# main.net
KiCad netlist of a schematic drawn in Altium Designer
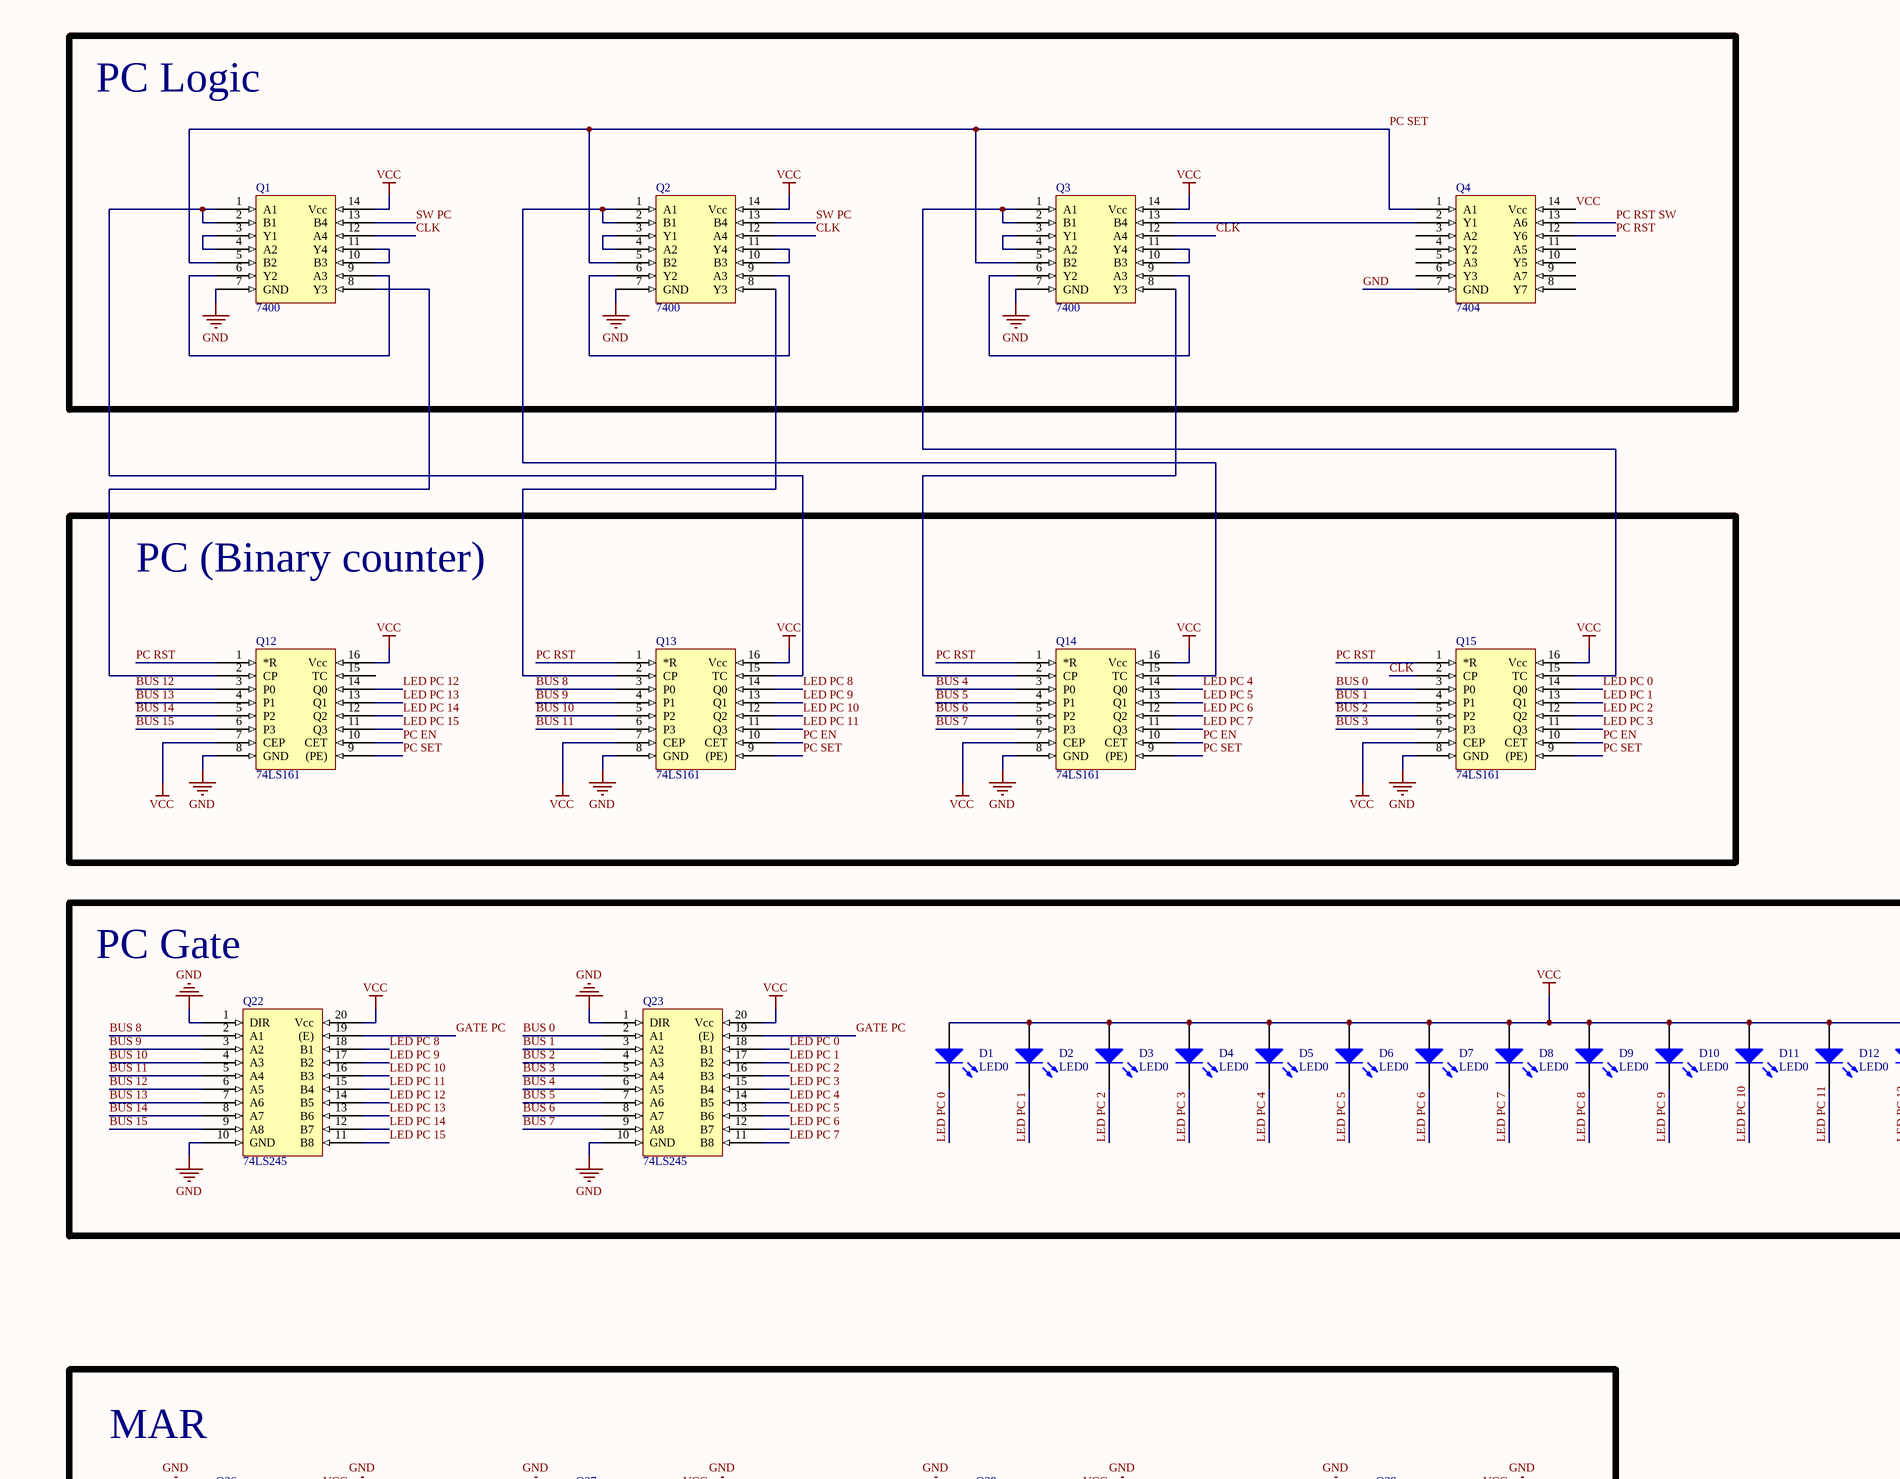
[diagram p0: main.SchDoc, top left]
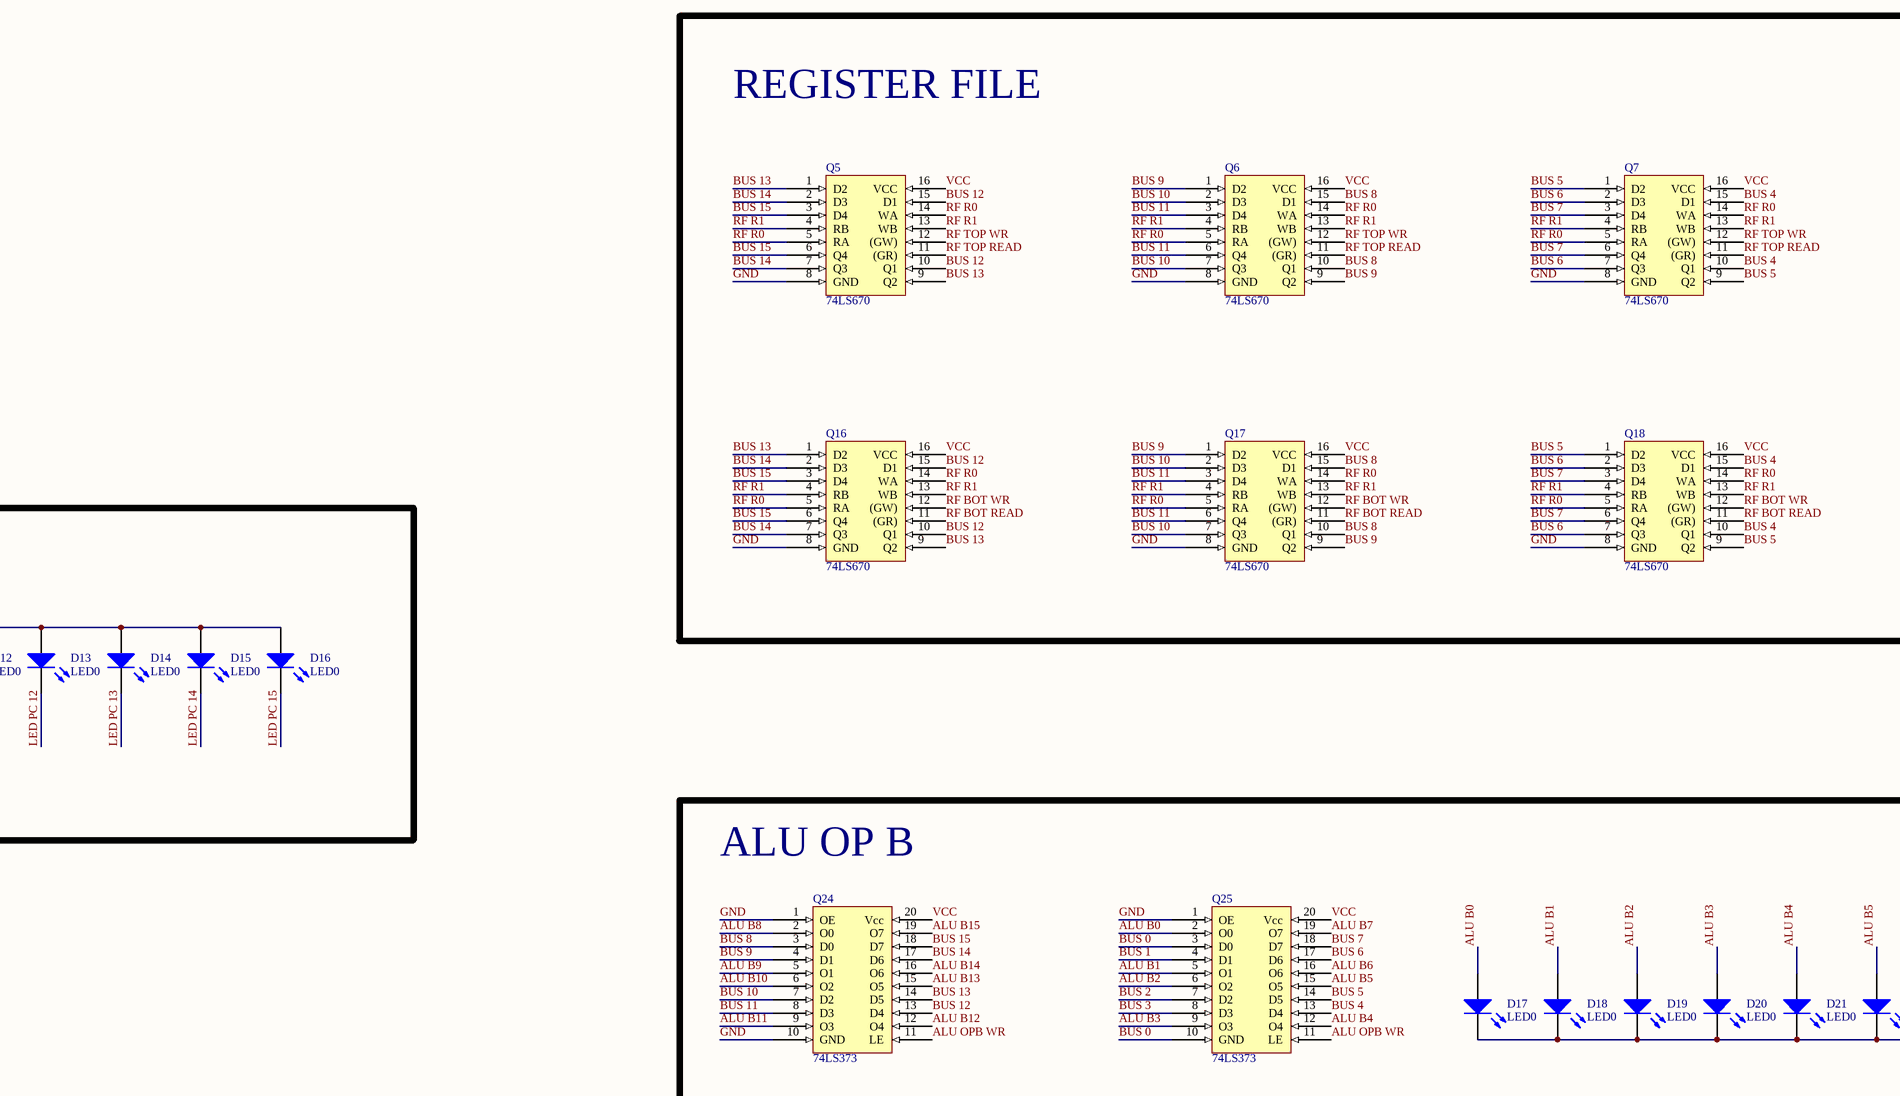
[diagram p1: main.SchDoc, top middle]
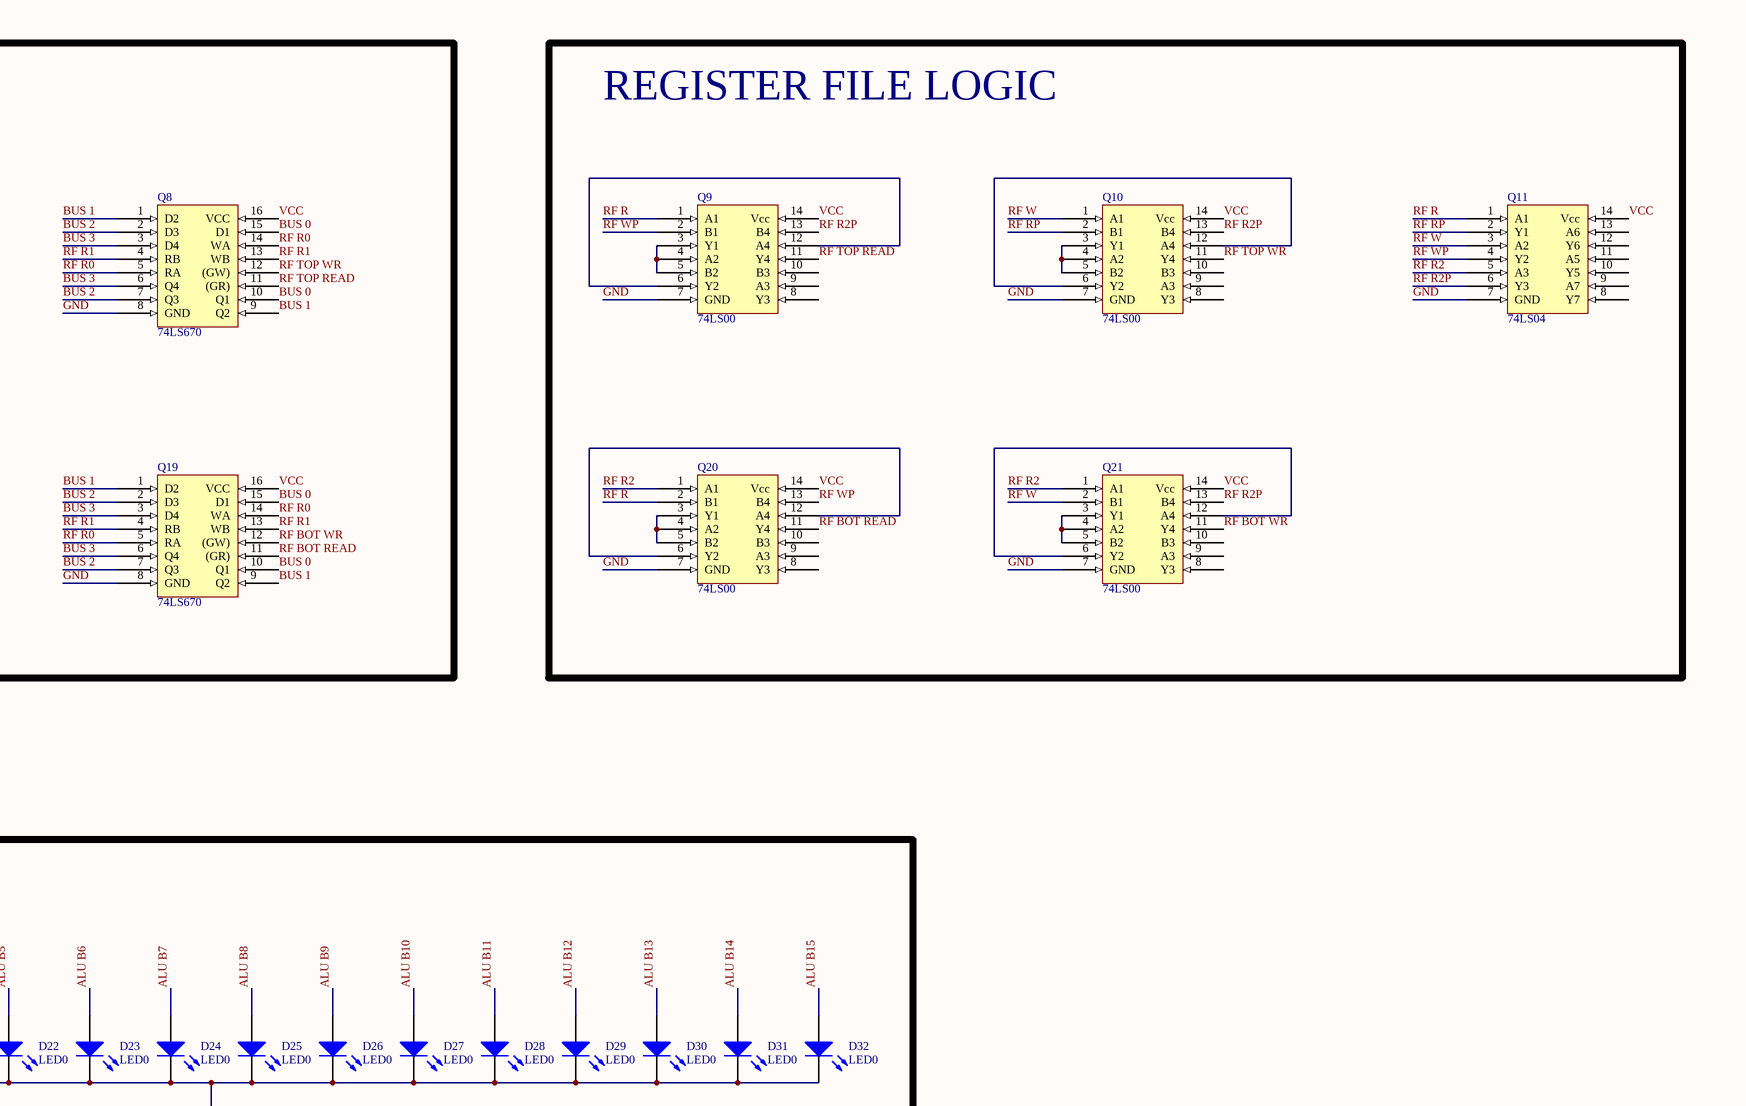
[diagram p2: main.SchDoc, top right]
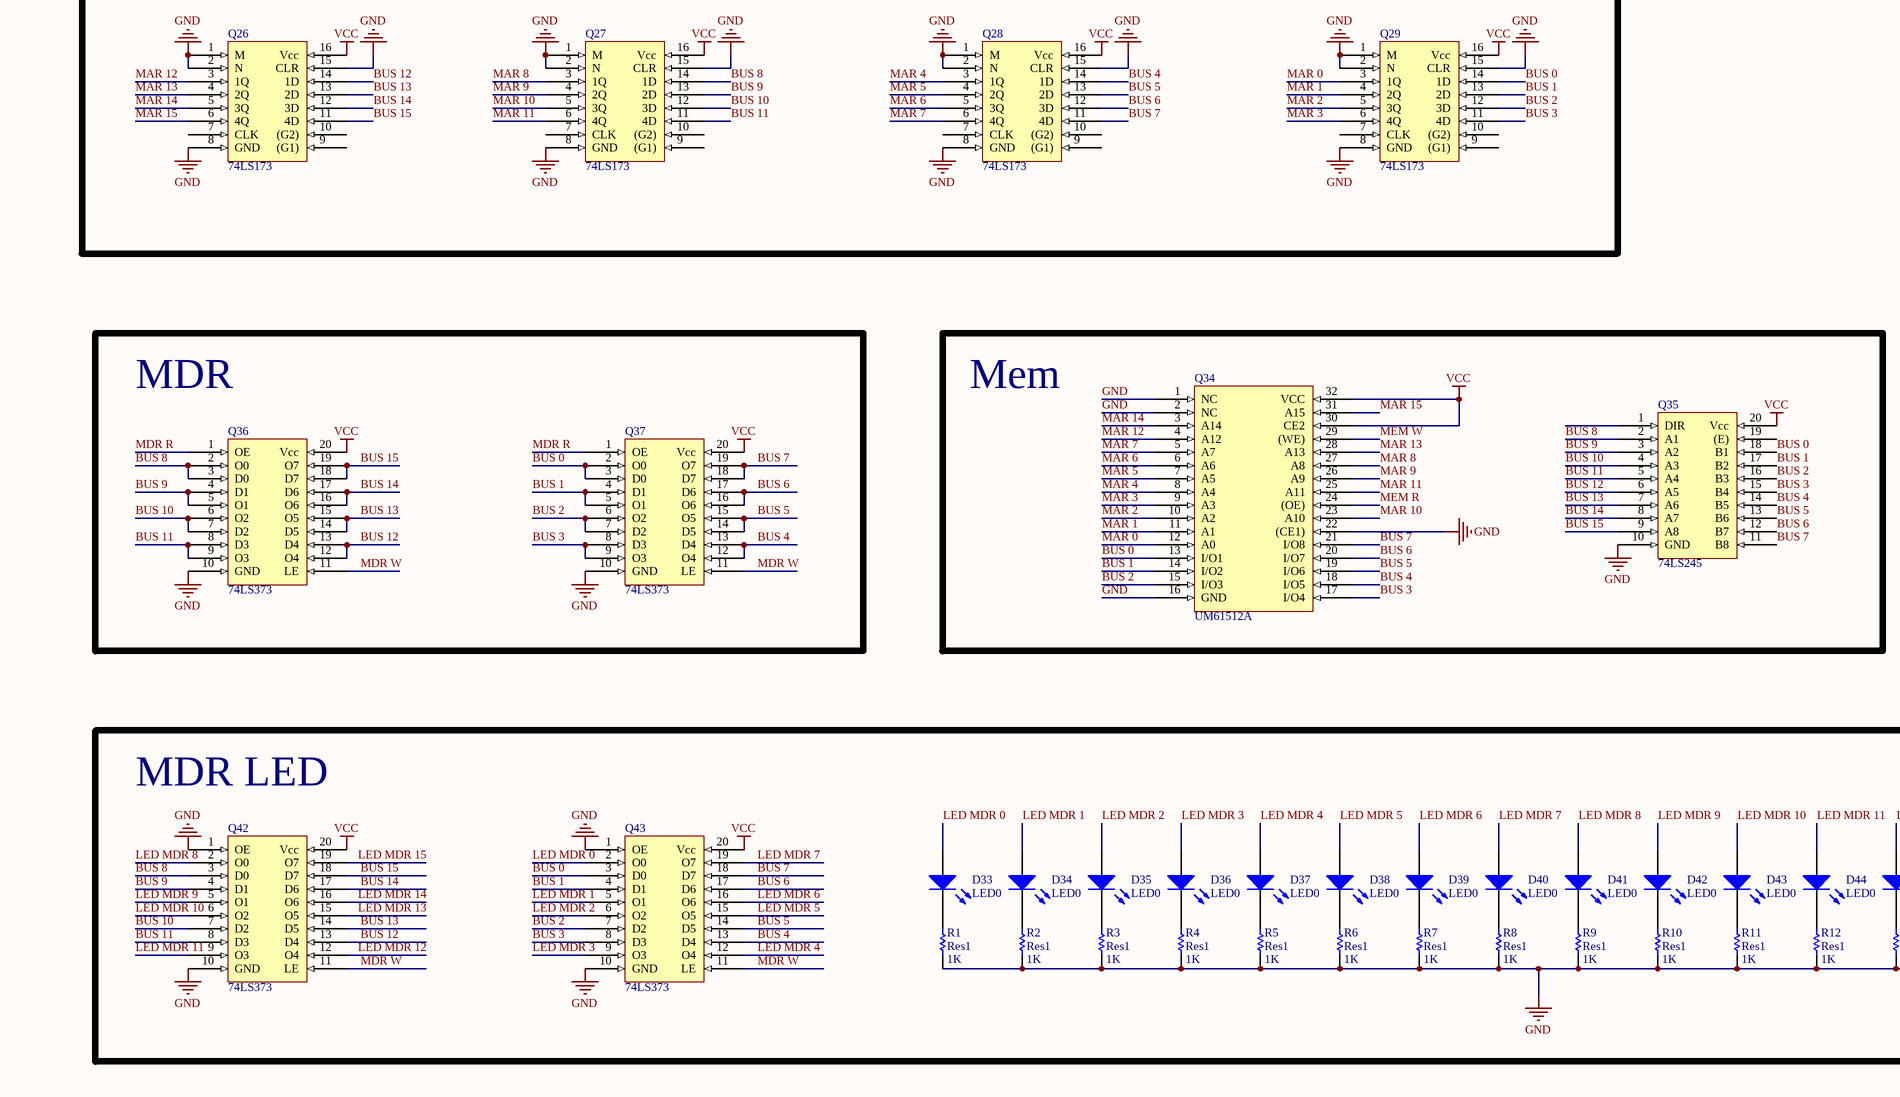
[diagram p3: main.SchDoc, centre left]
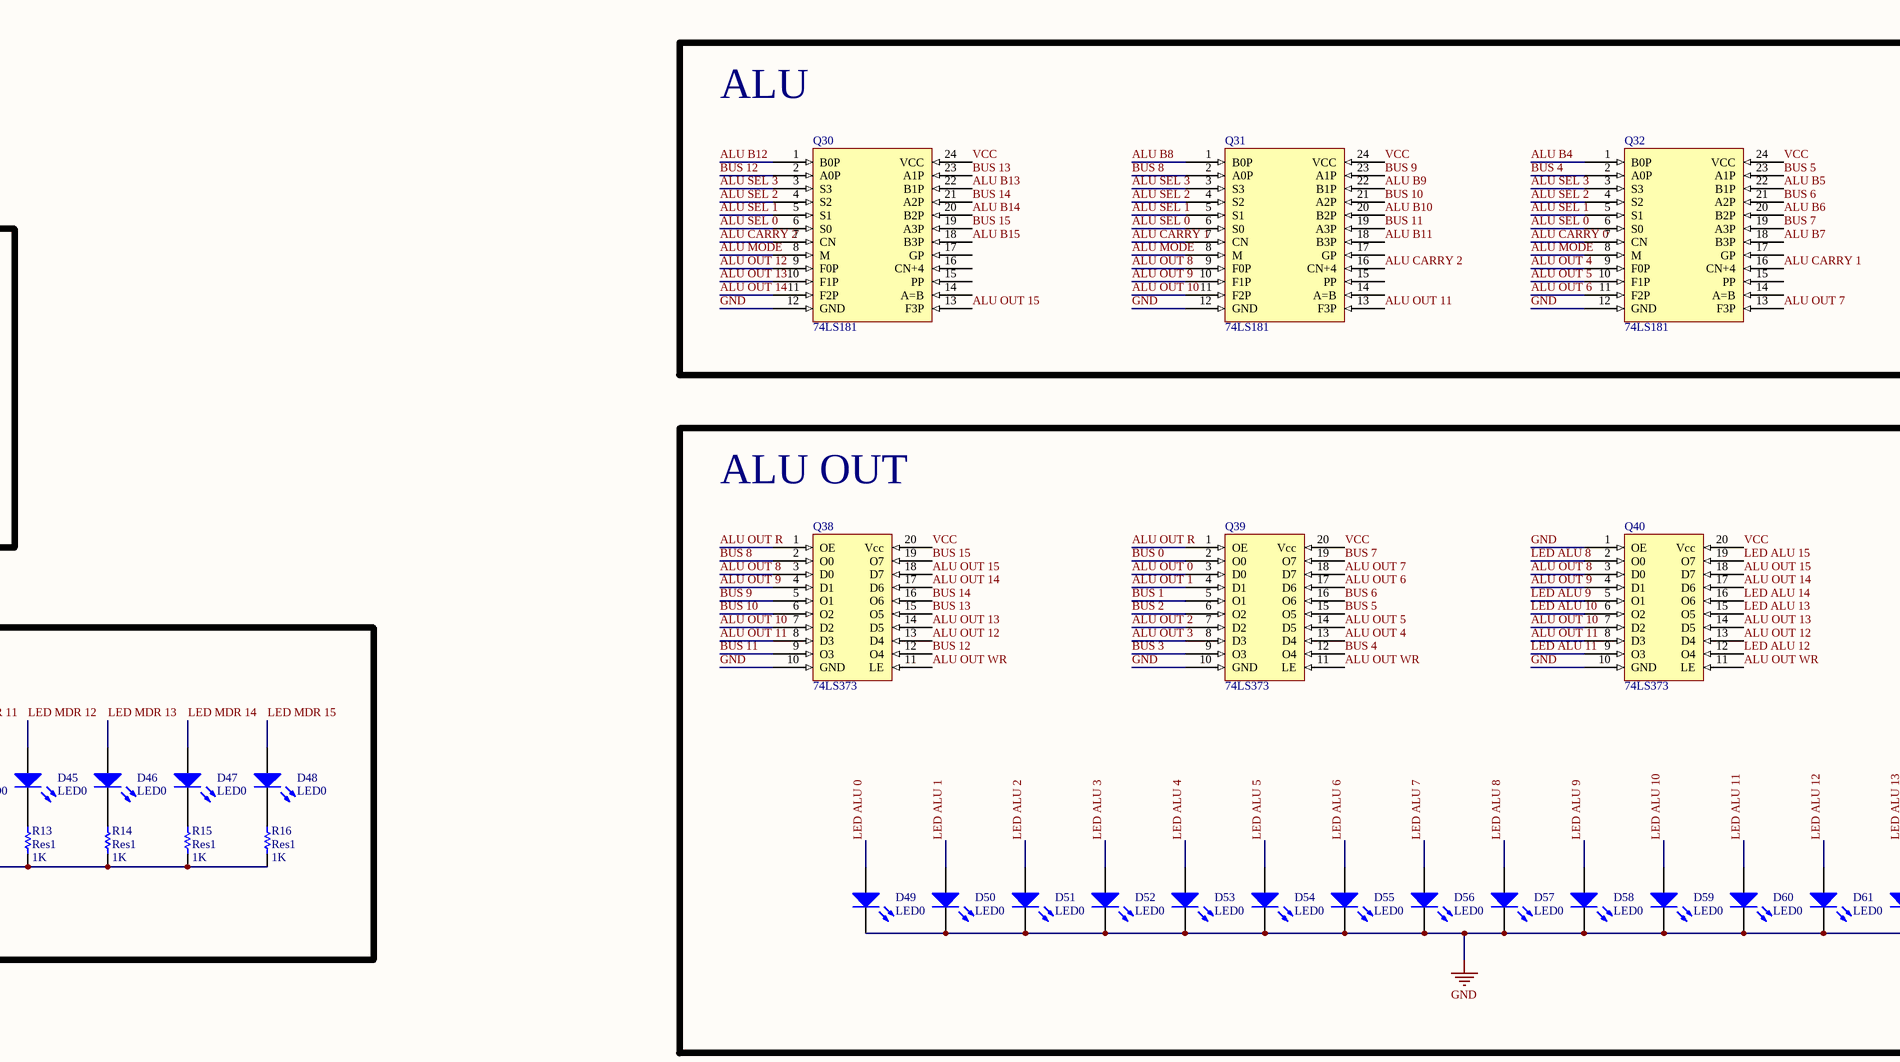
[diagram p4: main.SchDoc, centre middle]
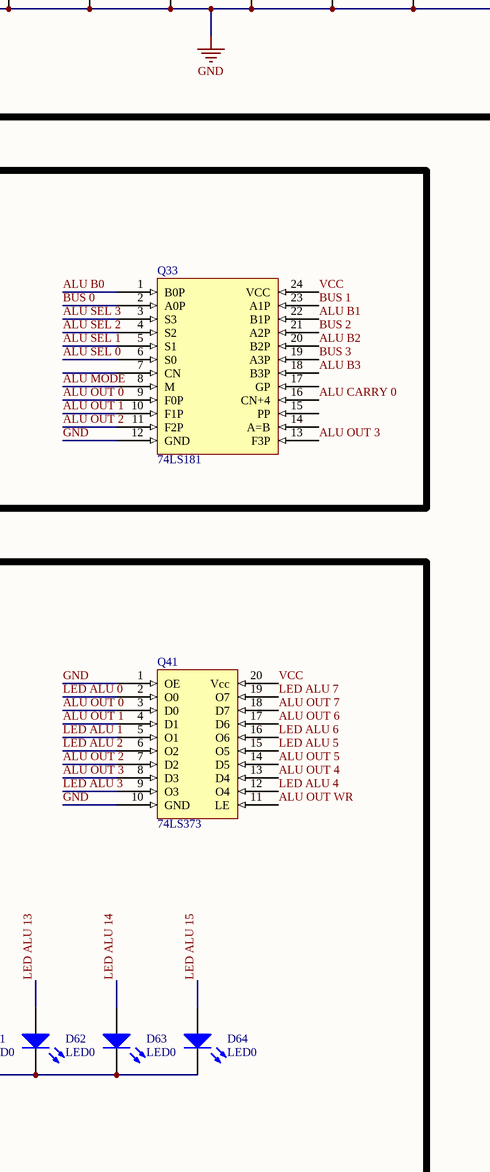
[diagram p5: main.SchDoc, centre right]
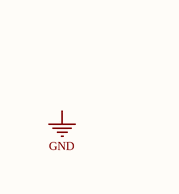
[diagram p6: main.SchDoc, bottom left]
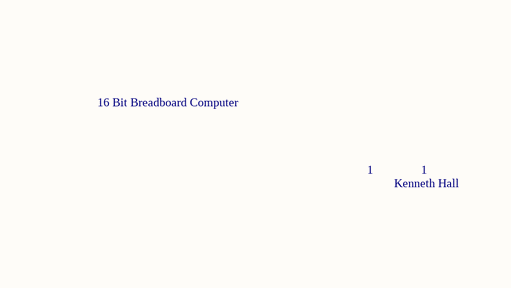
[diagram p7: main.SchDoc, bottom right]

(export (version "E")
  (design (tool "Eeschema 10.0.6"))
  (components
    (comp (ref "D1")
      (value "LED0")
      (footprint "LED-0")
      (description "Typical INFRARED GaAs LED")
      (fields (field (name "PUBLISHER") "Altium Limited"))
      (libsource (lib "Miscellaneous Devices") (part "LED0"))
    )
    (comp (ref "D2")
      (value "LED0")
      (footprint "LED-0")
      (description "Typical INFRARED GaAs LED")
      (fields (field (name "PUBLISHER") "Altium Limited"))
      (libsource (lib "Miscellaneous Devices") (part "LED0"))
    )
    (comp (ref "D3")
      (value "LED0")
      (footprint "LED-0")
      (description "Typical INFRARED GaAs LED")
      (fields (field (name "PUBLISHER") "Altium Limited"))
      (libsource (lib "Miscellaneous Devices") (part "LED0"))
    )
    (comp (ref "D4")
      (value "LED0")
      (footprint "LED-0")
      (description "Typical INFRARED GaAs LED")
      (fields (field (name "PUBLISHER") "Altium Limited"))
      (libsource (lib "Miscellaneous Devices") (part "LED0"))
    )
    (comp (ref "D5")
      (value "LED0")
      (footprint "LED-0")
      (description "Typical INFRARED GaAs LED")
      (fields (field (name "PUBLISHER") "Altium Limited"))
      (libsource (lib "Miscellaneous Devices") (part "LED0"))
    )
    (comp (ref "D6")
      (value "LED0")
      (footprint "LED-0")
      (description "Typical INFRARED GaAs LED")
      (fields (field (name "PUBLISHER") "Altium Limited"))
      (libsource (lib "Miscellaneous Devices") (part "LED0"))
    )
    (comp (ref "D7")
      (value "LED0")
      (footprint "LED-0")
      (description "Typical INFRARED GaAs LED")
      (fields (field (name "PUBLISHER") "Altium Limited"))
      (libsource (lib "Miscellaneous Devices") (part "LED0"))
    )
    (comp (ref "D8")
      (value "LED0")
      (footprint "LED-0")
      (description "Typical INFRARED GaAs LED")
      (fields (field (name "PUBLISHER") "Altium Limited"))
      (libsource (lib "Miscellaneous Devices") (part "LED0"))
    )
    (comp (ref "D9")
      (value "LED0")
      (footprint "LED-0")
      (description "Typical INFRARED GaAs LED")
      (fields (field (name "PUBLISHER") "Altium Limited"))
      (libsource (lib "Miscellaneous Devices") (part "LED0"))
    )
    (comp (ref "D10")
      (value "LED0")
      (footprint "LED-0")
      (description "Typical INFRARED GaAs LED")
      (fields (field (name "PUBLISHER") "Altium Limited"))
      (libsource (lib "Miscellaneous Devices") (part "LED0"))
    )
    (comp (ref "D11")
      (value "LED0")
      (footprint "LED-0")
      (description "Typical INFRARED GaAs LED")
      (fields (field (name "PUBLISHER") "Altium Limited"))
      (libsource (lib "Miscellaneous Devices") (part "LED0"))
    )
    (comp (ref "D12")
      (value "LED0")
      (footprint "LED-0")
      (description "Typical INFRARED GaAs LED")
      (fields (field (name "PUBLISHER") "Altium Limited"))
      (libsource (lib "Miscellaneous Devices") (part "LED0"))
    )
    (comp (ref "D13")
      (value "LED0")
      (footprint "LED-0")
      (description "Typical INFRARED GaAs LED")
      (fields (field (name "PUBLISHER") "Altium Limited"))
      (libsource (lib "Miscellaneous Devices") (part "LED0"))
    )
    (comp (ref "D14")
      (value "LED0")
      (footprint "LED-0")
      (description "Typical INFRARED GaAs LED")
      (fields (field (name "PUBLISHER") "Altium Limited"))
      (libsource (lib "Miscellaneous Devices") (part "LED0"))
    )
    (comp (ref "D15")
      (value "LED0")
      (footprint "LED-0")
      (description "Typical INFRARED GaAs LED")
      (fields (field (name "PUBLISHER") "Altium Limited"))
      (libsource (lib "Miscellaneous Devices") (part "LED0"))
    )
    (comp (ref "D16")
      (value "LED0")
      (footprint "LED-0")
      (description "Typical INFRARED GaAs LED")
      (fields (field (name "PUBLISHER") "Altium Limited"))
      (libsource (lib "Miscellaneous Devices") (part "LED0"))
    )
    (comp (ref "D17")
      (value "LED0")
      (footprint "LED-0")
      (description "Typical INFRARED GaAs LED")
      (fields (field (name "PUBLISHER") "Altium Limited"))
      (libsource (lib "Miscellaneous Devices") (part "LED0"))
    )
    (comp (ref "D18")
      (value "LED0")
      (footprint "LED-0")
      (description "Typical INFRARED GaAs LED")
      (fields (field (name "PUBLISHER") "Altium Limited"))
      (libsource (lib "Miscellaneous Devices") (part "LED0"))
    )
    (comp (ref "D19")
      (value "LED0")
      (footprint "LED-0")
      (description "Typical INFRARED GaAs LED")
      (fields (field (name "PUBLISHER") "Altium Limited"))
      (libsource (lib "Miscellaneous Devices") (part "LED0"))
    )
    (comp (ref "D20")
      (value "LED0")
      (footprint "LED-0")
      (description "Typical INFRARED GaAs LED")
      (fields (field (name "PUBLISHER") "Altium Limited"))
      (libsource (lib "Miscellaneous Devices") (part "LED0"))
    )
    (comp (ref "D21")
      (value "LED0")
      (footprint "LED-0")
      (description "Typical INFRARED GaAs LED")
      (fields (field (name "PUBLISHER") "Altium Limited"))
      (libsource (lib "Miscellaneous Devices") (part "LED0"))
    )
    (comp (ref "D22")
      (value "LED0")
      (footprint "LED-0")
      (description "Typical INFRARED GaAs LED")
      (fields (field (name "PUBLISHER") "Altium Limited"))
      (libsource (lib "Miscellaneous Devices") (part "LED0"))
    )
    (comp (ref "D23")
      (value "LED0")
      (footprint "LED-0")
      (description "Typical INFRARED GaAs LED")
      (fields (field (name "PUBLISHER") "Altium Limited"))
      (libsource (lib "Miscellaneous Devices") (part "LED0"))
    )
    (comp (ref "D24")
      (value "LED0")
      (footprint "LED-0")
      (description "Typical INFRARED GaAs LED")
      (fields (field (name "PUBLISHER") "Altium Limited"))
      (libsource (lib "Miscellaneous Devices") (part "LED0"))
    )
    (comp (ref "D25")
      (value "LED0")
      (footprint "LED-0")
      (description "Typical INFRARED GaAs LED")
      (fields (field (name "PUBLISHER") "Altium Limited"))
      (libsource (lib "Miscellaneous Devices") (part "LED0"))
    )
    (comp (ref "D26")
      (value "LED0")
      (footprint "LED-0")
      (description "Typical INFRARED GaAs LED")
      (fields (field (name "PUBLISHER") "Altium Limited"))
      (libsource (lib "Miscellaneous Devices") (part "LED0"))
    )
    (comp (ref "D27")
      (value "LED0")
      (footprint "LED-0")
      (description "Typical INFRARED GaAs LED")
      (fields (field (name "PUBLISHER") "Altium Limited"))
      (libsource (lib "Miscellaneous Devices") (part "LED0"))
    )
    (comp (ref "D28")
      (value "LED0")
      (footprint "LED-0")
      (description "Typical INFRARED GaAs LED")
      (fields (field (name "PUBLISHER") "Altium Limited"))
      (libsource (lib "Miscellaneous Devices") (part "LED0"))
    )
    (comp (ref "D29")
      (value "LED0")
      (footprint "LED-0")
      (description "Typical INFRARED GaAs LED")
      (fields (field (name "PUBLISHER") "Altium Limited"))
      (libsource (lib "Miscellaneous Devices") (part "LED0"))
    )
    (comp (ref "D30")
      (value "LED0")
      (footprint "LED-0")
      (description "Typical INFRARED GaAs LED")
      (fields (field (name "PUBLISHER") "Altium Limited"))
      (libsource (lib "Miscellaneous Devices") (part "LED0"))
    )
    (comp (ref "D31")
      (value "LED0")
      (footprint "LED-0")
      (description "Typical INFRARED GaAs LED")
      (fields (field (name "PUBLISHER") "Altium Limited"))
      (libsource (lib "Miscellaneous Devices") (part "LED0"))
    )
    (comp (ref "D32")
      (value "LED0")
      (footprint "LED-0")
      (description "Typical INFRARED GaAs LED")
      (fields (field (name "PUBLISHER") "Altium Limited"))
      (libsource (lib "Miscellaneous Devices") (part "LED0"))
    )
    (comp (ref "D33")
      (value "LED0")
      (footprint "LED-0")
      (description "Typical INFRARED GaAs LED")
      (fields (field (name "PUBLISHER") "Altium Limited"))
      (libsource (lib "Miscellaneous Devices") (part "LED0"))
    )
    (comp (ref "D34")
      (value "LED0")
      (footprint "LED-0")
      (description "Typical INFRARED GaAs LED")
      (fields (field (name "PUBLISHER") "Altium Limited"))
      (libsource (lib "Miscellaneous Devices") (part "LED0"))
    )
    (comp (ref "D35")
      (value "LED0")
      (footprint "LED-0")
      (description "Typical INFRARED GaAs LED")
      (fields (field (name "PUBLISHER") "Altium Limited"))
      (libsource (lib "Miscellaneous Devices") (part "LED0"))
    )
    (comp (ref "D36")
      (value "LED0")
      (footprint "LED-0")
      (description "Typical INFRARED GaAs LED")
      (fields (field (name "PUBLISHER") "Altium Limited"))
      (libsource (lib "Miscellaneous Devices") (part "LED0"))
    )
    (comp (ref "D37")
      (value "LED0")
      (footprint "LED-0")
      (description "Typical INFRARED GaAs LED")
      (fields (field (name "PUBLISHER") "Altium Limited"))
      (libsource (lib "Miscellaneous Devices") (part "LED0"))
    )
    (comp (ref "D38")
      (value "LED0")
      (footprint "LED-0")
      (description "Typical INFRARED GaAs LED")
      (fields (field (name "PUBLISHER") "Altium Limited"))
      (libsource (lib "Miscellaneous Devices") (part "LED0"))
    )
    (comp (ref "D39")
      (value "LED0")
      (footprint "LED-0")
      (description "Typical INFRARED GaAs LED")
      (fields (field (name "PUBLISHER") "Altium Limited"))
      (libsource (lib "Miscellaneous Devices") (part "LED0"))
    )
    (comp (ref "D40")
      (value "LED0")
      (footprint "LED-0")
      (description "Typical INFRARED GaAs LED")
      (fields (field (name "PUBLISHER") "Altium Limited"))
      (libsource (lib "Miscellaneous Devices") (part "LED0"))
    )
    (comp (ref "D41")
      (value "LED0")
      (footprint "LED-0")
      (description "Typical INFRARED GaAs LED")
      (fields (field (name "PUBLISHER") "Altium Limited"))
      (libsource (lib "Miscellaneous Devices") (part "LED0"))
    )
    (comp (ref "D42")
      (value "LED0")
      (footprint "LED-0")
      (description "Typical INFRARED GaAs LED")
      (fields (field (name "PUBLISHER") "Altium Limited"))
      (libsource (lib "Miscellaneous Devices") (part "LED0"))
    )
    (comp (ref "D43")
      (value "LED0")
      (footprint "LED-0")
      (description "Typical INFRARED GaAs LED")
      (fields (field (name "PUBLISHER") "Altium Limited"))
      (libsource (lib "Miscellaneous Devices") (part "LED0"))
    )
    (comp (ref "D44")
      (value "LED0")
      (footprint "LED-0")
      (description "Typical INFRARED GaAs LED")
      (fields (field (name "PUBLISHER") "Altium Limited"))
      (libsource (lib "Miscellaneous Devices") (part "LED0"))
    )
    (comp (ref "D45")
      (value "LED0")
      (footprint "LED-0")
      (description "Typical INFRARED GaAs LED")
      (fields (field (name "PUBLISHER") "Altium Limited"))
      (libsource (lib "Miscellaneous Devices") (part "LED0"))
    )
    (comp (ref "D46")
      (value "LED0")
      (footprint "LED-0")
      (description "Typical INFRARED GaAs LED")
      (fields (field (name "PUBLISHER") "Altium Limited"))
      (libsource (lib "Miscellaneous Devices") (part "LED0"))
    )
    (comp (ref "D47")
      (value "LED0")
      (footprint "LED-0")
      (description "Typical INFRARED GaAs LED")
      (fields (field (name "PUBLISHER") "Altium Limited"))
      (libsource (lib "Miscellaneous Devices") (part "LED0"))
    )
    (comp (ref "D48")
      (value "LED0")
      (footprint "LED-0")
      (description "Typical INFRARED GaAs LED")
      (fields (field (name "PUBLISHER") "Altium Limited"))
      (libsource (lib "Miscellaneous Devices") (part "LED0"))
    )
    (comp (ref "D49")
      (value "LED0")
      (footprint "LED-0")
      (description "Typical INFRARED GaAs LED")
      (fields (field (name "PUBLISHER") "Altium Limited"))
      (libsource (lib "Miscellaneous Devices") (part "LED0"))
    )
    (comp (ref "D50")
      (value "LED0")
      (footprint "LED-0")
      (description "Typical INFRARED GaAs LED")
      (fields (field (name "PUBLISHER") "Altium Limited"))
      (libsource (lib "Miscellaneous Devices") (part "LED0"))
    )
    (comp (ref "D51")
      (value "LED0")
      (footprint "LED-0")
      (description "Typical INFRARED GaAs LED")
      (fields (field (name "PUBLISHER") "Altium Limited"))
      (libsource (lib "Miscellaneous Devices") (part "LED0"))
    )
    (comp (ref "D52")
      (value "LED0")
      (footprint "LED-0")
      (description "Typical INFRARED GaAs LED")
      (fields (field (name "PUBLISHER") "Altium Limited"))
      (libsource (lib "Miscellaneous Devices") (part "LED0"))
    )
    (comp (ref "D53")
      (value "LED0")
      (footprint "LED-0")
      (description "Typical INFRARED GaAs LED")
      (fields (field (name "PUBLISHER") "Altium Limited"))
      (libsource (lib "Miscellaneous Devices") (part "LED0"))
    )
    (comp (ref "D54")
      (value "LED0")
      (footprint "LED-0")
      (description "Typical INFRARED GaAs LED")
      (fields (field (name "PUBLISHER") "Altium Limited"))
      (libsource (lib "Miscellaneous Devices") (part "LED0"))
    )
    (comp (ref "D55")
      (value "LED0")
      (footprint "LED-0")
      (description "Typical INFRARED GaAs LED")
      (fields (field (name "PUBLISHER") "Altium Limited"))
      (libsource (lib "Miscellaneous Devices") (part "LED0"))
    )
    (comp (ref "D56")
      (value "LED0")
      (footprint "LED-0")
      (description "Typical INFRARED GaAs LED")
      (fields (field (name "PUBLISHER") "Altium Limited"))
      (libsource (lib "Miscellaneous Devices") (part "LED0"))
    )
    (comp (ref "D57")
      (value "LED0")
      (footprint "LED-0")
      (description "Typical INFRARED GaAs LED")
      (fields (field (name "PUBLISHER") "Altium Limited"))
      (libsource (lib "Miscellaneous Devices") (part "LED0"))
    )
    (comp (ref "D58")
      (value "LED0")
      (footprint "LED-0")
      (description "Typical INFRARED GaAs LED")
      (fields (field (name "PUBLISHER") "Altium Limited"))
      (libsource (lib "Miscellaneous Devices") (part "LED0"))
    )
    (comp (ref "D59")
      (value "LED0")
      (footprint "LED-0")
      (description "Typical INFRARED GaAs LED")
      (fields (field (name "PUBLISHER") "Altium Limited"))
      (libsource (lib "Miscellaneous Devices") (part "LED0"))
    )
    (comp (ref "D60")
      (value "LED0")
      (footprint "LED-0")
      (description "Typical INFRARED GaAs LED")
      (fields (field (name "PUBLISHER") "Altium Limited"))
      (libsource (lib "Miscellaneous Devices") (part "LED0"))
    )
    (comp (ref "D61")
      (value "LED0")
      (footprint "LED-0")
      (description "Typical INFRARED GaAs LED")
      (fields (field (name "PUBLISHER") "Altium Limited"))
      (libsource (lib "Miscellaneous Devices") (part "LED0"))
    )
    (comp (ref "D62")
      (value "LED0")
      (footprint "LED-0")
      (description "Typical INFRARED GaAs LED")
      (fields (field (name "PUBLISHER") "Altium Limited"))
      (libsource (lib "Miscellaneous Devices") (part "LED0"))
    )
    (comp (ref "D63")
      (value "LED0")
      (footprint "LED-0")
      (description "Typical INFRARED GaAs LED")
      (fields (field (name "PUBLISHER") "Altium Limited"))
      (libsource (lib "Miscellaneous Devices") (part "LED0"))
    )
    (comp (ref "D64")
      (value "LED0")
      (footprint "LED-0")
      (description "Typical INFRARED GaAs LED")
      (fields (field (name "PUBLISHER") "Altium Limited"))
      (libsource (lib "Miscellaneous Devices") (part "LED0"))
    )
    (comp (ref "Q1")
      (value "7400")
      (footprint "DIP14")
      (description "4-BIT BINARY COUNTERS")
      (libsource (lib "mylibrary") (part "7400"))
    )
    (comp (ref "Q2")
      (value "7400")
      (footprint "DIP14")
      (description "4-BIT BINARY COUNTERS")
      (libsource (lib "mylibrary") (part "7400"))
    )
    (comp (ref "Q3")
      (value "7400")
      (footprint "DIP14")
      (description "4-BIT BINARY COUNTERS")
      (libsource (lib "mylibrary") (part "7400"))
    )
    (comp (ref "Q4")
      (value "7404")
      (footprint "DIP14")
      (description "Hex Inverting Gates")
      (libsource (lib "mylibrary") (part "7404"))
    )
    (comp (ref "Q5")
      (value "74LS670")
      (footprint "DIP16")
      (description "4-BY-4 REGISTER FILES WITH 3-STATE OUTPUTS")
      (libsource (lib "mylibrary") (part "74LS670"))
    )
    (comp (ref "Q6")
      (value "74LS670")
      (footprint "DIP16")
      (description "4-BY-4 REGISTER FILES WITH 3-STATE OUTPUTS")
      (libsource (lib "mylibrary") (part "74LS670"))
    )
    (comp (ref "Q7")
      (value "74LS670")
      (footprint "DIP16")
      (description "4-BY-4 REGISTER FILES WITH 3-STATE OUTPUTS")
      (libsource (lib "mylibrary") (part "74LS670"))
    )
    (comp (ref "Q8")
      (value "74LS670")
      (footprint "DIP16")
      (description "4-BY-4 REGISTER FILES WITH 3-STATE OUTPUTS")
      (libsource (lib "mylibrary") (part "74LS670"))
    )
    (comp (ref "Q9")
      (value "74LS00")
      (footprint "DIP14")
      (description "Quad 2-Input NAND Gate")
      (libsource (lib "mylibrary") (part "74LS00"))
    )
    (comp (ref "Q10")
      (value "74LS00")
      (footprint "DIP14")
      (description "Quad 2-Input NAND Gate")
      (libsource (lib "mylibrary") (part "74LS00"))
    )
    (comp (ref "Q11")
      (value "74LS04")
      (footprint "DIP14")
      (description "Hex Inverting Gates")
      (libsource (lib "mylibrary") (part "74LS04"))
    )
    (comp (ref "Q12")
      (value "74LS161")
      (footprint "DIP16")
      (description "4-BIT BINARY COUNTERS")
      (libsource (lib "mylibrary") (part "74LS161"))
    )
    (comp (ref "Q13")
      (value "74LS161")
      (footprint "DIP16")
      (description "4-BIT BINARY COUNTERS")
      (libsource (lib "mylibrary") (part "74LS161"))
    )
    (comp (ref "Q14")
      (value "74LS161")
      (footprint "DIP16")
      (description "4-BIT BINARY COUNTERS")
      (libsource (lib "mylibrary") (part "74LS161"))
    )
    (comp (ref "Q15")
      (value "74LS161")
      (footprint "DIP16")
      (description "4-BIT BINARY COUNTERS")
      (libsource (lib "mylibrary") (part "74LS161"))
    )
    (comp (ref "Q16")
      (value "74LS670")
      (footprint "DIP16")
      (description "4-BY-4 REGISTER FILES WITH 3-STATE OUTPUTS")
      (libsource (lib "mylibrary") (part "74LS670"))
    )
    (comp (ref "Q17")
      (value "74LS670")
      (footprint "DIP16")
      (description "4-BY-4 REGISTER FILES WITH 3-STATE OUTPUTS")
      (libsource (lib "mylibrary") (part "74LS670"))
    )
    (comp (ref "Q18")
      (value "74LS670")
      (footprint "DIP16")
      (description "4-BY-4 REGISTER FILES WITH 3-STATE OUTPUTS")
      (libsource (lib "mylibrary") (part "74LS670"))
    )
    (comp (ref "Q19")
      (value "74LS670")
      (footprint "DIP16")
      (description "4-BY-4 REGISTER FILES WITH 3-STATE OUTPUTS")
      (libsource (lib "mylibrary") (part "74LS670"))
    )
    (comp (ref "Q20")
      (value "74LS00")
      (footprint "DIP14")
      (description "Quad 2-Input NAND Gate")
      (libsource (lib "mylibrary") (part "74LS00"))
    )
    (comp (ref "Q21")
      (value "74LS00")
      (footprint "DIP14")
      (description "Quad 2-Input NAND Gate")
      (libsource (lib "mylibrary") (part "74LS00"))
    )
    (comp (ref "Q22")
      (value "74LS245")
      (footprint "DIP20")
      (description "OCTAL BUS TRANSCEIVER")
      (libsource (lib "mylibrary") (part "74LS245"))
    )
    (comp (ref "Q23")
      (value "74LS245")
      (footprint "DIP20")
      (description "OCTAL BUS TRANSCEIVER")
      (libsource (lib "mylibrary") (part "74LS245"))
    )
    (comp (ref "Q24")
      (value "74LS373")
      (footprint "DIP20")
      (description "OCTAL TRANSPARENT LATCH WITH 3-STATE OUTPUTS")
      (libsource (lib "mylibrary") (part "74LS373"))
    )
    (comp (ref "Q25")
      (value "74LS373")
      (footprint "DIP20")
      (description "OCTAL TRANSPARENT LATCH WITH 3-STATE OUTPUTS")
      (libsource (lib "mylibrary") (part "74LS373"))
    )
    (comp (ref "Q26")
      (value "74LS173")
      (footprint "DIP16")
      (description "4-BIT D-TYPE REGISTERS WITH 3-STATE OUTPUTS")
      (libsource (lib "mylibrary") (part "74LS173"))
    )
    (comp (ref "Q27")
      (value "74LS173")
      (footprint "DIP16")
      (description "4-BIT D-TYPE REGISTERS WITH 3-STATE OUTPUTS")
      (libsource (lib "mylibrary") (part "74LS173"))
    )
    (comp (ref "Q28")
      (value "74LS173")
      (footprint "DIP16")
      (description "4-BIT D-TYPE REGISTERS WITH 3-STATE OUTPUTS")
      (libsource (lib "mylibrary") (part "74LS173"))
    )
    (comp (ref "Q29")
      (value "74LS173")
      (footprint "DIP16")
      (description "4-BIT D-TYPE REGISTERS WITH 3-STATE OUTPUTS")
      (libsource (lib "mylibrary") (part "74LS173"))
    )
    (comp (ref "Q30")
      (value "74LS181")
      (footprint "DIP24")
      (description "4-Bit Arithmetic Logic Unit")
      (libsource (lib "mylibrary") (part "74LS181"))
    )
    (comp (ref "Q31")
      (value "74LS181")
      (footprint "DIP24")
      (description "4-Bit Arithmetic Logic Unit")
      (libsource (lib "mylibrary") (part "74LS181"))
    )
    (comp (ref "Q32")
      (value "74LS181")
      (footprint "DIP24")
      (description "4-Bit Arithmetic Logic Unit")
      (libsource (lib "mylibrary") (part "74LS181"))
    )
    (comp (ref "Q33")
      (value "74LS181")
      (footprint "DIP24")
      (description "4-Bit Arithmetic Logic Unit")
      (libsource (lib "mylibrary") (part "74LS181"))
    )
    (comp (ref "Q34")
      (value "UM61512A")
      (footprint "DIP32")
      (description "64K X 8 BIT HIGH SPEED CMOS SRAM")
      (libsource (lib "mylibrary") (part "UM61512A"))
    )
    (comp (ref "Q35")
      (value "74LS245")
      (footprint "DIP20")
      (description "OCTAL BUS TRANSCEIVER")
      (libsource (lib "mylibrary") (part "74LS245"))
    )
    (comp (ref "Q36")
      (value "74LS373")
      (footprint "DIP20")
      (description "OCTAL TRANSPARENT LATCH WITH 3-STATE OUTPUTS")
      (libsource (lib "mylibrary") (part "74LS373"))
    )
    (comp (ref "Q37")
      (value "74LS373")
      (footprint "DIP20")
      (description "OCTAL TRANSPARENT LATCH WITH 3-STATE OUTPUTS")
      (libsource (lib "mylibrary") (part "74LS373"))
    )
    (comp (ref "Q38")
      (value "74LS373")
      (footprint "DIP20")
      (description "OCTAL TRANSPARENT LATCH WITH 3-STATE OUTPUTS")
      (libsource (lib "mylibrary") (part "74LS373"))
    )
    (comp (ref "Q39")
      (value "74LS373")
      (footprint "DIP20")
      (description "OCTAL TRANSPARENT LATCH WITH 3-STATE OUTPUTS")
      (libsource (lib "mylibrary") (part "74LS373"))
    )
    (comp (ref "Q40")
      (value "74LS373")
      (footprint "DIP20")
      (description "OCTAL TRANSPARENT LATCH WITH 3-STATE OUTPUTS")
      (libsource (lib "mylibrary") (part "74LS373"))
    )
    (comp (ref "Q41")
      (value "74LS373")
      (footprint "DIP20")
      (description "OCTAL TRANSPARENT LATCH WITH 3-STATE OUTPUTS")
      (libsource (lib "mylibrary") (part "74LS373"))
    )
    (comp (ref "Q42")
      (value "74LS373")
      (footprint "DIP20")
      (description "OCTAL TRANSPARENT LATCH WITH 3-STATE OUTPUTS")
      (libsource (lib "mylibrary") (part "74LS373"))
    )
    (comp (ref "Q43")
      (value "74LS373")
      (footprint "DIP20")
      (description "OCTAL TRANSPARENT LATCH WITH 3-STATE OUTPUTS")
      (libsource (lib "mylibrary") (part "74LS373"))
    )
    (comp (ref "R1")
      (value "Res1")
      (footprint "AXIAL-0.3")
      (description "Resistor")
      (fields (field (name "ALTIUM_VALUE") "1K") (field (name "PUBLISHER") "Altium Limited"))
      (libsource (lib "Miscellaneous Devices") (part "Res1"))
    )
    (comp (ref "R2")
      (value "Res1")
      (footprint "AXIAL-0.3")
      (description "Resistor")
      (fields (field (name "ALTIUM_VALUE") "1K") (field (name "PUBLISHER") "Altium Limited"))
      (libsource (lib "Miscellaneous Devices") (part "Res1"))
    )
    (comp (ref "R3")
      (value "Res1")
      (footprint "AXIAL-0.3")
      (description "Resistor")
      (fields (field (name "ALTIUM_VALUE") "1K") (field (name "PUBLISHER") "Altium Limited"))
      (libsource (lib "Miscellaneous Devices") (part "Res1"))
    )
    (comp (ref "R4")
      (value "Res1")
      (footprint "AXIAL-0.3")
      (description "Resistor")
      (fields (field (name "ALTIUM_VALUE") "1K") (field (name "PUBLISHER") "Altium Limited"))
      (libsource (lib "Miscellaneous Devices") (part "Res1"))
    )
    (comp (ref "R5")
      (value "Res1")
      (footprint "AXIAL-0.3")
      (description "Resistor")
      (fields (field (name "ALTIUM_VALUE") "1K") (field (name "PUBLISHER") "Altium Limited"))
      (libsource (lib "Miscellaneous Devices") (part "Res1"))
    )
    (comp (ref "R6")
      (value "Res1")
      (footprint "AXIAL-0.3")
      (description "Resistor")
      (fields (field (name "ALTIUM_VALUE") "1K") (field (name "PUBLISHER") "Altium Limited"))
      (libsource (lib "Miscellaneous Devices") (part "Res1"))
    )
    (comp (ref "R7")
      (value "Res1")
      (footprint "AXIAL-0.3")
      (description "Resistor")
      (fields (field (name "ALTIUM_VALUE") "1K") (field (name "PUBLISHER") "Altium Limited"))
      (libsource (lib "Miscellaneous Devices") (part "Res1"))
    )
    (comp (ref "R8")
      (value "Res1")
      (footprint "AXIAL-0.3")
      (description "Resistor")
      (fields (field (name "ALTIUM_VALUE") "1K") (field (name "PUBLISHER") "Altium Limited"))
      (libsource (lib "Miscellaneous Devices") (part "Res1"))
    )
    (comp (ref "R9")
      (value "Res1")
      (footprint "AXIAL-0.3")
      (description "Resistor")
      (fields (field (name "ALTIUM_VALUE") "1K") (field (name "PUBLISHER") "Altium Limited"))
      (libsource (lib "Miscellaneous Devices") (part "Res1"))
    )
    (comp (ref "R10")
      (value "Res1")
      (footprint "AXIAL-0.3")
      (description "Resistor")
      (fields (field (name "ALTIUM_VALUE") "1K") (field (name "PUBLISHER") "Altium Limited"))
      (libsource (lib "Miscellaneous Devices") (part "Res1"))
    )
    (comp (ref "R11")
      (value "Res1")
      (footprint "AXIAL-0.3")
      (description "Resistor")
      (fields (field (name "ALTIUM_VALUE") "1K") (field (name "PUBLISHER") "Altium Limited"))
      (libsource (lib "Miscellaneous Devices") (part "Res1"))
    )
    (comp (ref "R12")
      (value "Res1")
      (footprint "AXIAL-0.3")
      (description "Resistor")
      (fields (field (name "ALTIUM_VALUE") "1K") (field (name "PUBLISHER") "Altium Limited"))
      (libsource (lib "Miscellaneous Devices") (part "Res1"))
    )
    (comp (ref "R13")
      (value "Res1")
      (footprint "AXIAL-0.3")
      (description "Resistor")
      (fields (field (name "ALTIUM_VALUE") "1K") (field (name "PUBLISHER") "Altium Limited"))
      (libsource (lib "Miscellaneous Devices") (part "Res1"))
    )
    (comp (ref "R14")
      (value "Res1")
      (footprint "AXIAL-0.3")
      (description "Resistor")
      (fields (field (name "ALTIUM_VALUE") "1K") (field (name "PUBLISHER") "Altium Limited"))
      (libsource (lib "Miscellaneous Devices") (part "Res1"))
    )
    (comp (ref "R15")
      (value "Res1")
      (footprint "AXIAL-0.3")
      (description "Resistor")
      (fields (field (name "ALTIUM_VALUE") "1K") (field (name "PUBLISHER") "Altium Limited"))
      (libsource (lib "Miscellaneous Devices") (part "Res1"))
    )
    (comp (ref "R16")
      (value "Res1")
      (footprint "AXIAL-0.3")
      (description "Resistor")
      (fields (field (name "ALTIUM_VALUE") "1K") (field (name "PUBLISHER") "Altium Limited"))
      (libsource (lib "Miscellaneous Devices") (part "Res1"))
    )
  )
  (nets
    (net (code "1") (name "/ALU B0") (class "Default")
      (node (ref "D17") (pin "1") (pinfunction "A_1") (pintype "passive"))
      (node (ref "Q25") (pin "2") (pinfunction "O0_2") (pintype "input"))
      (node (ref "Q33") (pin "1") (pinfunction "B0P_1") (pintype "input"))
    )
    (net (code "2") (name "/ALU B1") (class "Default")
      (node (ref "D18") (pin "1") (pinfunction "A_1") (pintype "passive"))
      (node (ref "Q25") (pin "5") (pinfunction "O1_5") (pintype "input"))
      (node (ref "Q33") (pin "22") (pinfunction "B1P_22") (pintype "input"))
    )
    (net (code "3") (name "/ALU B2") (class "Default")
      (node (ref "D19") (pin "1") (pinfunction "A_1") (pintype "passive"))
      (node (ref "Q25") (pin "6") (pinfunction "O2_6") (pintype "input"))
      (node (ref "Q33") (pin "20") (pinfunction "B2P_20") (pintype "input"))
    )
    (net (code "4") (name "/ALU B3") (class "Default")
      (node (ref "D20") (pin "1") (pinfunction "A_1") (pintype "passive"))
      (node (ref "Q25") (pin "9") (pinfunction "O3_9") (pintype "input"))
      (node (ref "Q33") (pin "18") (pinfunction "B3P_18") (pintype "input"))
    )
    (net (code "5") (name "/ALU B4") (class "Default")
      (node (ref "D21") (pin "1") (pinfunction "A_1") (pintype "passive"))
      (node (ref "Q25") (pin "12") (pinfunction "O4_12") (pintype "input"))
      (node (ref "Q32") (pin "1") (pinfunction "B0P_1") (pintype "input"))
    )
    (net (code "6") (name "/ALU B5") (class "Default")
      (node (ref "D22") (pin "1") (pinfunction "A_1") (pintype "passive"))
      (node (ref "Q25") (pin "15") (pinfunction "O5_15") (pintype "input"))
      (node (ref "Q32") (pin "22") (pinfunction "B1P_22") (pintype "input"))
    )
    (net (code "7") (name "/ALU B6") (class "Default")
      (node (ref "D23") (pin "1") (pinfunction "A_1") (pintype "passive"))
      (node (ref "Q25") (pin "16") (pinfunction "O6_16") (pintype "input"))
      (node (ref "Q32") (pin "20") (pinfunction "B2P_20") (pintype "input"))
    )
    (net (code "8") (name "/ALU B7") (class "Default")
      (node (ref "D24") (pin "1") (pinfunction "A_1") (pintype "passive"))
      (node (ref "Q25") (pin "19") (pinfunction "O7_19") (pintype "input"))
      (node (ref "Q32") (pin "18") (pinfunction "B3P_18") (pintype "input"))
    )
    (net (code "9") (name "/ALU B8") (class "Default")
      (node (ref "D25") (pin "1") (pinfunction "A_1") (pintype "passive"))
      (node (ref "Q24") (pin "2") (pinfunction "O0_2") (pintype "input"))
      (node (ref "Q31") (pin "1") (pinfunction "B0P_1") (pintype "input"))
    )
    (net (code "10") (name "/ALU B9") (class "Default")
      (node (ref "D26") (pin "1") (pinfunction "A_1") (pintype "passive"))
      (node (ref "Q24") (pin "5") (pinfunction "O1_5") (pintype "input"))
      (node (ref "Q31") (pin "22") (pinfunction "B1P_22") (pintype "input"))
    )
    (net (code "11") (name "/ALU B10") (class "Default")
      (node (ref "D27") (pin "1") (pinfunction "A_1") (pintype "passive"))
      (node (ref "Q24") (pin "6") (pinfunction "O2_6") (pintype "input"))
      (node (ref "Q31") (pin "20") (pinfunction "B2P_20") (pintype "input"))
    )
    (net (code "12") (name "/ALU B11") (class "Default")
      (node (ref "D28") (pin "1") (pinfunction "A_1") (pintype "passive"))
      (node (ref "Q24") (pin "9") (pinfunction "O3_9") (pintype "input"))
      (node (ref "Q31") (pin "18") (pinfunction "B3P_18") (pintype "input"))
    )
    (net (code "13") (name "/ALU B12") (class "Default")
      (node (ref "D29") (pin "1") (pinfunction "A_1") (pintype "passive"))
      (node (ref "Q24") (pin "12") (pinfunction "O4_12") (pintype "input"))
      (node (ref "Q30") (pin "1") (pinfunction "B0P_1") (pintype "input"))
    )
    (net (code "14") (name "/ALU B13") (class "Default")
      (node (ref "D30") (pin "1") (pinfunction "A_1") (pintype "passive"))
      (node (ref "Q24") (pin "15") (pinfunction "O5_15") (pintype "input"))
      (node (ref "Q30") (pin "22") (pinfunction "B1P_22") (pintype "input"))
    )
    (net (code "15") (name "/ALU B14") (class "Default")
      (node (ref "D31") (pin "1") (pinfunction "A_1") (pintype "passive"))
      (node (ref "Q24") (pin "16") (pinfunction "O6_16") (pintype "input"))
      (node (ref "Q30") (pin "20") (pinfunction "B2P_20") (pintype "input"))
    )
    (net (code "16") (name "/ALU B15") (class "Default")
      (node (ref "D32") (pin "1") (pinfunction "A_1") (pintype "passive"))
      (node (ref "Q24") (pin "19") (pinfunction "O7_19") (pintype "input"))
      (node (ref "Q30") (pin "18") (pinfunction "B3P_18") (pintype "input"))
    )
    (net (code "17") (name "/ALU CARRY 0") (class "Default")
      (node (ref "Q32") (pin "7") (pinfunction "CN_7") (pintype "input"))
      (node (ref "Q33") (pin "16") (pinfunction "CN+4_16") (pintype "input"))
    )
    (net (code "18") (name "/ALU CARRY 1") (class "Default")
      (node (ref "Q31") (pin "7") (pinfunction "CN_7") (pintype "input"))
      (node (ref "Q32") (pin "16") (pinfunction "CN+4_16") (pintype "input"))
    )
    (net (code "19") (name "/ALU CARRY 2") (class "Default")
      (node (ref "Q30") (pin "7") (pinfunction "CN_7") (pintype "input"))
      (node (ref "Q31") (pin "16") (pinfunction "CN+4_16") (pintype "input"))
    )
    (net (code "20") (name "/ALU MODE") (class "Default")
      (node (ref "Q30") (pin "8") (pinfunction "M_8") (pintype "input"))
      (node (ref "Q31") (pin "8") (pinfunction "M_8") (pintype "input"))
      (node (ref "Q32") (pin "8") (pinfunction "M_8") (pintype "input"))
      (node (ref "Q33") (pin "8") (pinfunction "M_8") (pintype "input"))
    )
    (net (code "21") (name "/ALU OPB WR") (class "Default")
      (node (ref "Q24") (pin "11") (pinfunction "LE_11") (pintype "input"))
      (node (ref "Q25") (pin "11") (pinfunction "LE_11") (pintype "input"))
    )
    (net (code "22") (name "/ALU OUT 0") (class "Default")
      (node (ref "Q33") (pin "9") (pinfunction "F0P_9") (pintype "input"))
      (node (ref "Q39") (pin "3") (pinfunction "D0_3") (pintype "input"))
      (node (ref "Q41") (pin "3") (pinfunction "D0_3") (pintype "input"))
    )
    (net (code "23") (name "/ALU OUT 1") (class "Default")
      (node (ref "Q33") (pin "10") (pinfunction "F1P_10") (pintype "input"))
      (node (ref "Q39") (pin "4") (pinfunction "D1_4") (pintype "input"))
      (node (ref "Q41") (pin "4") (pinfunction "D1_4") (pintype "input"))
    )
    (net (code "24") (name "/ALU OUT 2") (class "Default")
      (node (ref "Q33") (pin "11") (pinfunction "F2P_11") (pintype "input"))
      (node (ref "Q39") (pin "7") (pinfunction "D2_7") (pintype "input"))
      (node (ref "Q41") (pin "7") (pinfunction "D2_7") (pintype "input"))
    )
    (net (code "25") (name "/ALU OUT 3") (class "Default")
      (node (ref "Q33") (pin "13") (pinfunction "F3P_13") (pintype "input"))
      (node (ref "Q39") (pin "8") (pinfunction "D3_8") (pintype "input"))
      (node (ref "Q41") (pin "8") (pinfunction "D3_8") (pintype "input"))
    )
    (net (code "26") (name "/ALU OUT 4") (class "Default")
      (node (ref "Q32") (pin "9") (pinfunction "F0P_9") (pintype "input"))
      (node (ref "Q39") (pin "13") (pinfunction "D4_13") (pintype "input"))
      (node (ref "Q41") (pin "13") (pinfunction "D4_13") (pintype "input"))
    )
    (net (code "27") (name "/ALU OUT 5") (class "Default")
      (node (ref "Q32") (pin "10") (pinfunction "F1P_10") (pintype "input"))
      (node (ref "Q39") (pin "14") (pinfunction "D5_14") (pintype "input"))
      (node (ref "Q41") (pin "14") (pinfunction "D5_14") (pintype "input"))
    )
    (net (code "28") (name "/ALU OUT 6") (class "Default")
      (node (ref "Q32") (pin "11") (pinfunction "F2P_11") (pintype "input"))
      (node (ref "Q39") (pin "17") (pinfunction "D6_17") (pintype "input"))
      (node (ref "Q41") (pin "17") (pinfunction "D6_17") (pintype "input"))
    )
    (net (code "29") (name "/ALU OUT 7") (class "Default")
      (node (ref "Q32") (pin "13") (pinfunction "F3P_13") (pintype "input"))
      (node (ref "Q39") (pin "18") (pinfunction "D7_18") (pintype "input"))
      (node (ref "Q41") (pin "18") (pinfunction "D7_18") (pintype "input"))
    )
    (net (code "30") (name "/ALU OUT 8") (class "Default")
      (node (ref "Q31") (pin "9") (pinfunction "F0P_9") (pintype "input"))
      (node (ref "Q38") (pin "3") (pinfunction "D0_3") (pintype "input"))
      (node (ref "Q40") (pin "3") (pinfunction "D0_3") (pintype "input"))
    )
    (net (code "31") (name "/ALU OUT 9") (class "Default")
      (node (ref "Q31") (pin "10") (pinfunction "F1P_10") (pintype "input"))
      (node (ref "Q38") (pin "4") (pinfunction "D1_4") (pintype "input"))
      (node (ref "Q40") (pin "4") (pinfunction "D1_4") (pintype "input"))
    )
    (net (code "32") (name "/ALU OUT 10") (class "Default")
      (node (ref "Q31") (pin "11") (pinfunction "F2P_11") (pintype "input"))
      (node (ref "Q38") (pin "7") (pinfunction "D2_7") (pintype "input"))
      (node (ref "Q40") (pin "7") (pinfunction "D2_7") (pintype "input"))
    )
    (net (code "33") (name "/ALU OUT 11") (class "Default")
      (node (ref "Q31") (pin "13") (pinfunction "F3P_13") (pintype "input"))
      (node (ref "Q38") (pin "8") (pinfunction "D3_8") (pintype "input"))
      (node (ref "Q40") (pin "8") (pinfunction "D3_8") (pintype "input"))
    )
    (net (code "34") (name "/ALU OUT 12") (class "Default")
      (node (ref "Q30") (pin "9") (pinfunction "F0P_9") (pintype "input"))
      (node (ref "Q38") (pin "13") (pinfunction "D4_13") (pintype "input"))
      (node (ref "Q40") (pin "13") (pinfunction "D4_13") (pintype "input"))
    )
    (net (code "35") (name "/ALU OUT 13") (class "Default")
      (node (ref "Q30") (pin "10") (pinfunction "F1P_10") (pintype "input"))
      (node (ref "Q38") (pin "14") (pinfunction "D5_14") (pintype "input"))
      (node (ref "Q40") (pin "14") (pinfunction "D5_14") (pintype "input"))
    )
    (net (code "36") (name "/ALU OUT 14") (class "Default")
      (node (ref "Q30") (pin "11") (pinfunction "F2P_11") (pintype "input"))
      (node (ref "Q38") (pin "17") (pinfunction "D6_17") (pintype "input"))
      (node (ref "Q40") (pin "17") (pinfunction "D6_17") (pintype "input"))
    )
    (net (code "37") (name "/ALU OUT 15") (class "Default")
      (node (ref "Q30") (pin "13") (pinfunction "F3P_13") (pintype "input"))
      (node (ref "Q38") (pin "18") (pinfunction "D7_18") (pintype "input"))
      (node (ref "Q40") (pin "18") (pinfunction "D7_18") (pintype "input"))
    )
    (net (code "38") (name "/ALU OUT R") (class "Default")
      (node (ref "Q38") (pin "1") (pinfunction "OE_1") (pintype "input"))
      (node (ref "Q39") (pin "1") (pinfunction "OE_1") (pintype "input"))
    )
    (net (code "39") (name "/ALU OUT WR") (class "Default")
      (node (ref "Q38") (pin "11") (pinfunction "LE_11") (pintype "input"))
      (node (ref "Q39") (pin "11") (pinfunction "LE_11") (pintype "input"))
      (node (ref "Q40") (pin "11") (pinfunction "LE_11") (pintype "input"))
      (node (ref "Q41") (pin "11") (pinfunction "LE_11") (pintype "input"))
    )
    (net (code "40") (name "/ALU SEL 0") (class "Default")
      (node (ref "Q30") (pin "6") (pinfunction "S0_6") (pintype "input"))
      (node (ref "Q31") (pin "6") (pinfunction "S0_6") (pintype "input"))
      (node (ref "Q32") (pin "6") (pinfunction "S0_6") (pintype "input"))
      (node (ref "Q33") (pin "6") (pinfunction "S0_6") (pintype "input"))
    )
    (net (code "41") (name "/ALU SEL 1") (class "Default")
      (node (ref "Q30") (pin "5") (pinfunction "S1_5") (pintype "input"))
      (node (ref "Q31") (pin "5") (pinfunction "S1_5") (pintype "input"))
      (node (ref "Q32") (pin "5") (pinfunction "S1_5") (pintype "input"))
      (node (ref "Q33") (pin "5") (pinfunction "S1_5") (pintype "input"))
    )
    (net (code "42") (name "/ALU SEL 2") (class "Default")
      (node (ref "Q30") (pin "4") (pinfunction "S2_4") (pintype "input"))
      (node (ref "Q31") (pin "4") (pinfunction "S2_4") (pintype "input"))
      (node (ref "Q32") (pin "4") (pinfunction "S2_4") (pintype "input"))
      (node (ref "Q33") (pin "4") (pinfunction "S2_4") (pintype "input"))
    )
    (net (code "43") (name "/ALU SEL 3") (class "Default")
      (node (ref "Q30") (pin "3") (pinfunction "S3_3") (pintype "input"))
      (node (ref "Q31") (pin "3") (pinfunction "S3_3") (pintype "input"))
      (node (ref "Q32") (pin "3") (pinfunction "S3_3") (pintype "input"))
      (node (ref "Q33") (pin "3") (pinfunction "S3_3") (pintype "input"))
    )
    (net (code "44") (name "/BUS 0") (class "Default")
      (node (ref "Q15") (pin "3") (pinfunction "P0_3") (pintype "input"))
      (node (ref "Q19") (pin "10") (pinfunction "Q1_10") (pintype "input"))
      (node (ref "Q19") (pin "15") (pinfunction "D1_15") (pintype "input"))
      (node (ref "Q23") (pin "2") (pinfunction "A1_2") (pintype "input"))
      (node (ref "Q25") (pin "10") (pinfunction "GND_10") (pintype "input"))
      (node (ref "Q25") (pin "3") (pinfunction "D0_3") (pintype "input"))
      (node (ref "Q29") (pin "14") (pinfunction "1D_14") (pintype "input"))
      (node (ref "Q33") (pin "2") (pinfunction "A0P_2") (pintype "input"))
      (node (ref "Q34") (pin "13") (pinfunction "I/O1_13") (pintype "input"))
      (node (ref "Q35") (pin "18") (pinfunction "B1_18") (pintype "input"))
      (node (ref "Q37") (pin "2") (pinfunction "O0_2") (pintype "input"))
      (node (ref "Q37") (pin "3") (pinfunction "D0_3") (pintype "input"))
      (node (ref "Q39") (pin "2") (pinfunction "O0_2") (pintype "input"))
      (node (ref "Q43") (pin "3") (pinfunction "D0_3") (pintype "input"))
      (node (ref "Q8") (pin "10") (pinfunction "Q1_10") (pintype "input"))
      (node (ref "Q8") (pin "15") (pinfunction "D1_15") (pintype "input"))
    )
    (net (code "45") (name "/BUS 1") (class "Default")
      (node (ref "Q15") (pin "4") (pinfunction "P1_4") (pintype "input"))
      (node (ref "Q19") (pin "1") (pinfunction "D2_1") (pintype "input"))
      (node (ref "Q19") (pin "9") (pinfunction "Q2_9") (pintype "input"))
      (node (ref "Q23") (pin "3") (pinfunction "A2_3") (pintype "input"))
      (node (ref "Q25") (pin "4") (pinfunction "D1_4") (pintype "input"))
      (node (ref "Q29") (pin "13") (pinfunction "2D_13") (pintype "input"))
      (node (ref "Q33") (pin "23") (pinfunction "A1P_23") (pintype "input"))
      (node (ref "Q34") (pin "14") (pinfunction "I/O2_14") (pintype "input"))
      (node (ref "Q35") (pin "17") (pinfunction "B2_17") (pintype "input"))
      (node (ref "Q37") (pin "4") (pinfunction "D1_4") (pintype "input"))
      (node (ref "Q37") (pin "5") (pinfunction "O1_5") (pintype "input"))
      (node (ref "Q39") (pin "5") (pinfunction "O1_5") (pintype "input"))
      (node (ref "Q43") (pin "4") (pinfunction "D1_4") (pintype "input"))
      (node (ref "Q8") (pin "1") (pinfunction "D2_1") (pintype "input"))
      (node (ref "Q8") (pin "9") (pinfunction "Q2_9") (pintype "input"))
    )
    (net (code "46") (name "/BUS 2") (class "Default")
      (node (ref "Q15") (pin "5") (pinfunction "P2_5") (pintype "input"))
      (node (ref "Q19") (pin "2") (pinfunction "D3_2") (pintype "input"))
      (node (ref "Q19") (pin "7") (pinfunction "Q3_7") (pintype "input"))
      (node (ref "Q23") (pin "4") (pinfunction "A3_4") (pintype "input"))
      (node (ref "Q25") (pin "7") (pinfunction "D2_7") (pintype "input"))
      (node (ref "Q29") (pin "12") (pinfunction "3D_12") (pintype "input"))
      (node (ref "Q33") (pin "21") (pinfunction "A2P_21") (pintype "input"))
      (node (ref "Q34") (pin "15") (pinfunction "I/O3_15") (pintype "input"))
      (node (ref "Q35") (pin "16") (pinfunction "B3_16") (pintype "input"))
      (node (ref "Q37") (pin "6") (pinfunction "O2_6") (pintype "input"))
      (node (ref "Q37") (pin "7") (pinfunction "D2_7") (pintype "input"))
      (node (ref "Q39") (pin "6") (pinfunction "O2_6") (pintype "input"))
      (node (ref "Q43") (pin "7") (pinfunction "D2_7") (pintype "input"))
      (node (ref "Q8") (pin "2") (pinfunction "D3_2") (pintype "input"))
      (node (ref "Q8") (pin "7") (pinfunction "Q3_7") (pintype "input"))
    )
    (net (code "47") (name "/BUS 3") (class "Default")
      (node (ref "Q15") (pin "6") (pinfunction "P3_6") (pintype "input"))
      (node (ref "Q19") (pin "3") (pinfunction "D4_3") (pintype "input"))
      (node (ref "Q19") (pin "6") (pinfunction "Q4_6") (pintype "input"))
      (node (ref "Q23") (pin "5") (pinfunction "A4_5") (pintype "input"))
      (node (ref "Q25") (pin "8") (pinfunction "D3_8") (pintype "input"))
      (node (ref "Q29") (pin "11") (pinfunction "4D_11") (pintype "input"))
      (node (ref "Q33") (pin "19") (pinfunction "A3P_19") (pintype "input"))
      (node (ref "Q34") (pin "17") (pinfunction "I/O4_17") (pintype "input"))
      (node (ref "Q35") (pin "15") (pinfunction "B4_15") (pintype "input"))
      (node (ref "Q37") (pin "8") (pinfunction "D3_8") (pintype "input"))
      (node (ref "Q37") (pin "9") (pinfunction "O3_9") (pintype "input"))
      (node (ref "Q39") (pin "9") (pinfunction "O3_9") (pintype "input"))
      (node (ref "Q43") (pin "8") (pinfunction "D3_8") (pintype "input"))
      (node (ref "Q8") (pin "3") (pinfunction "D4_3") (pintype "input"))
      (node (ref "Q8") (pin "6") (pinfunction "Q4_6") (pintype "input"))
    )
    (net (code "48") (name "/BUS 4") (class "Default")
      (node (ref "Q14") (pin "3") (pinfunction "P0_3") (pintype "input"))
      (node (ref "Q18") (pin "10") (pinfunction "Q1_10") (pintype "input"))
      (node (ref "Q18") (pin "15") (pinfunction "D1_15") (pintype "input"))
      (node (ref "Q23") (pin "6") (pinfunction "A5_6") (pintype "input"))
      (node (ref "Q25") (pin "13") (pinfunction "D4_13") (pintype "input"))
      (node (ref "Q28") (pin "14") (pinfunction "1D_14") (pintype "input"))
      (node (ref "Q32") (pin "2") (pinfunction "A0P_2") (pintype "input"))
      (node (ref "Q34") (pin "18") (pinfunction "I/O5_18") (pintype "input"))
      (node (ref "Q35") (pin "14") (pinfunction "B5_14") (pintype "input"))
      (node (ref "Q37") (pin "12") (pinfunction "O4_12") (pintype "input"))
      (node (ref "Q37") (pin "13") (pinfunction "D4_13") (pintype "input"))
      (node (ref "Q39") (pin "12") (pinfunction "O4_12") (pintype "input"))
      (node (ref "Q43") (pin "13") (pinfunction "D4_13") (pintype "input"))
      (node (ref "Q7") (pin "10") (pinfunction "Q1_10") (pintype "input"))
      (node (ref "Q7") (pin "15") (pinfunction "D1_15") (pintype "input"))
    )
    (net (code "49") (name "/BUS 5") (class "Default")
      (node (ref "Q14") (pin "4") (pinfunction "P1_4") (pintype "input"))
      (node (ref "Q18") (pin "1") (pinfunction "D2_1") (pintype "input"))
      (node (ref "Q18") (pin "9") (pinfunction "Q2_9") (pintype "input"))
      (node (ref "Q23") (pin "7") (pinfunction "A6_7") (pintype "input"))
      (node (ref "Q25") (pin "14") (pinfunction "D5_14") (pintype "input"))
      (node (ref "Q28") (pin "13") (pinfunction "2D_13") (pintype "input"))
      (node (ref "Q32") (pin "23") (pinfunction "A1P_23") (pintype "input"))
      (node (ref "Q34") (pin "19") (pinfunction "I/O6_19") (pintype "input"))
      (node (ref "Q35") (pin "13") (pinfunction "B6_13") (pintype "input"))
      (node (ref "Q37") (pin "14") (pinfunction "D5_14") (pintype "input"))
      (node (ref "Q37") (pin "15") (pinfunction "O5_15") (pintype "input"))
      (node (ref "Q39") (pin "15") (pinfunction "O5_15") (pintype "input"))
      (node (ref "Q43") (pin "14") (pinfunction "D5_14") (pintype "input"))
      (node (ref "Q7") (pin "1") (pinfunction "D2_1") (pintype "input"))
      (node (ref "Q7") (pin "9") (pinfunction "Q2_9") (pintype "input"))
    )
    (net (code "50") (name "/BUS 6") (class "Default")
      (node (ref "Q14") (pin "5") (pinfunction "P2_5") (pintype "input"))
      (node (ref "Q18") (pin "2") (pinfunction "D3_2") (pintype "input"))
      (node (ref "Q18") (pin "7") (pinfunction "Q3_7") (pintype "input"))
      (node (ref "Q23") (pin "8") (pinfunction "A7_8") (pintype "input"))
      (node (ref "Q25") (pin "17") (pinfunction "D6_17") (pintype "input"))
      (node (ref "Q28") (pin "12") (pinfunction "3D_12") (pintype "input"))
      (node (ref "Q32") (pin "21") (pinfunction "A2P_21") (pintype "input"))
      (node (ref "Q34") (pin "20") (pinfunction "I/O7_20") (pintype "input"))
      (node (ref "Q35") (pin "12") (pinfunction "B7_12") (pintype "input"))
      (node (ref "Q37") (pin "16") (pinfunction "O6_16") (pintype "input"))
      (node (ref "Q37") (pin "17") (pinfunction "D6_17") (pintype "input"))
      (node (ref "Q39") (pin "16") (pinfunction "O6_16") (pintype "input"))
      (node (ref "Q43") (pin "17") (pinfunction "D6_17") (pintype "input"))
      (node (ref "Q7") (pin "2") (pinfunction "D3_2") (pintype "input"))
      (node (ref "Q7") (pin "7") (pinfunction "Q3_7") (pintype "input"))
    )
    (net (code "51") (name "/BUS 7") (class "Default")
      (node (ref "Q14") (pin "6") (pinfunction "P3_6") (pintype "input"))
      (node (ref "Q18") (pin "3") (pinfunction "D4_3") (pintype "input"))
      (node (ref "Q18") (pin "6") (pinfunction "Q4_6") (pintype "input"))
      (node (ref "Q23") (pin "9") (pinfunction "A8_9") (pintype "input"))
      (node (ref "Q25") (pin "18") (pinfunction "D7_18") (pintype "input"))
      (node (ref "Q28") (pin "11") (pinfunction "4D_11") (pintype "input"))
      (node (ref "Q32") (pin "19") (pinfunction "A3P_19") (pintype "input"))
      (node (ref "Q34") (pin "21") (pinfunction "I/O8_21") (pintype "input"))
      (node (ref "Q35") (pin "11") (pinfunction "B8_11") (pintype "input"))
      (node (ref "Q37") (pin "18") (pinfunction "D7_18") (pintype "input"))
      (node (ref "Q37") (pin "19") (pinfunction "O7_19") (pintype "input"))
      (node (ref "Q39") (pin "19") (pinfunction "O7_19") (pintype "input"))
      (node (ref "Q43") (pin "18") (pinfunction "D7_18") (pintype "input"))
      (node (ref "Q7") (pin "3") (pinfunction "D4_3") (pintype "input"))
      (node (ref "Q7") (pin "6") (pinfunction "Q4_6") (pintype "input"))
    )
    (net (code "52") (name "/BUS 8") (class "Default")
      (node (ref "Q13") (pin "3") (pinfunction "P0_3") (pintype "input"))
      (node (ref "Q17") (pin "10") (pinfunction "Q1_10") (pintype "input"))
      (node (ref "Q17") (pin "15") (pinfunction "D1_15") (pintype "input"))
      (node (ref "Q22") (pin "2") (pinfunction "A1_2") (pintype "input"))
      (node (ref "Q24") (pin "3") (pinfunction "D0_3") (pintype "input"))
      (node (ref "Q27") (pin "14") (pinfunction "1D_14") (pintype "input"))
      (node (ref "Q31") (pin "2") (pinfunction "A0P_2") (pintype "input"))
      (node (ref "Q35") (pin "2") (pinfunction "A1_2") (pintype "input"))
      (node (ref "Q36") (pin "2") (pinfunction "O0_2") (pintype "input"))
      (node (ref "Q36") (pin "3") (pinfunction "D0_3") (pintype "input"))
      (node (ref "Q38") (pin "2") (pinfunction "O0_2") (pintype "input"))
      (node (ref "Q42") (pin "3") (pinfunction "D0_3") (pintype "input"))
      (node (ref "Q6") (pin "10") (pinfunction "Q1_10") (pintype "input"))
      (node (ref "Q6") (pin "15") (pinfunction "D1_15") (pintype "input"))
    )
    (net (code "53") (name "/BUS 9") (class "Default")
      (node (ref "Q13") (pin "4") (pinfunction "P1_4") (pintype "input"))
      (node (ref "Q17") (pin "1") (pinfunction "D2_1") (pintype "input"))
      (node (ref "Q17") (pin "9") (pinfunction "Q2_9") (pintype "input"))
      (node (ref "Q22") (pin "3") (pinfunction "A2_3") (pintype "input"))
      (node (ref "Q24") (pin "4") (pinfunction "D1_4") (pintype "input"))
      (node (ref "Q27") (pin "13") (pinfunction "2D_13") (pintype "input"))
      (node (ref "Q31") (pin "23") (pinfunction "A1P_23") (pintype "input"))
      (node (ref "Q35") (pin "3") (pinfunction "A2_3") (pintype "input"))
      (node (ref "Q36") (pin "4") (pinfunction "D1_4") (pintype "input"))
      (node (ref "Q36") (pin "5") (pinfunction "O1_5") (pintype "input"))
      (node (ref "Q38") (pin "5") (pinfunction "O1_5") (pintype "input"))
      (node (ref "Q42") (pin "4") (pinfunction "D1_4") (pintype "input"))
      (node (ref "Q6") (pin "1") (pinfunction "D2_1") (pintype "input"))
      (node (ref "Q6") (pin "9") (pinfunction "Q2_9") (pintype "input"))
    )
    (net (code "54") (name "/BUS 10") (class "Default")
      (node (ref "Q13") (pin "5") (pinfunction "P2_5") (pintype "input"))
      (node (ref "Q17") (pin "2") (pinfunction "D3_2") (pintype "input"))
      (node (ref "Q17") (pin "7") (pinfunction "Q3_7") (pintype "input"))
      (node (ref "Q22") (pin "4") (pinfunction "A3_4") (pintype "input"))
      (node (ref "Q24") (pin "7") (pinfunction "D2_7") (pintype "input"))
      (node (ref "Q27") (pin "12") (pinfunction "3D_12") (pintype "input"))
      (node (ref "Q31") (pin "21") (pinfunction "A2P_21") (pintype "input"))
      (node (ref "Q35") (pin "4") (pinfunction "A3_4") (pintype "input"))
      (node (ref "Q36") (pin "6") (pinfunction "O2_6") (pintype "input"))
      (node (ref "Q36") (pin "7") (pinfunction "D2_7") (pintype "input"))
      (node (ref "Q38") (pin "6") (pinfunction "O2_6") (pintype "input"))
      (node (ref "Q42") (pin "7") (pinfunction "D2_7") (pintype "input"))
      (node (ref "Q6") (pin "2") (pinfunction "D3_2") (pintype "input"))
      (node (ref "Q6") (pin "7") (pinfunction "Q3_7") (pintype "input"))
    )
    (net (code "55") (name "/BUS 11") (class "Default")
      (node (ref "Q13") (pin "6") (pinfunction "P3_6") (pintype "input"))
      (node (ref "Q17") (pin "3") (pinfunction "D4_3") (pintype "input"))
      (node (ref "Q17") (pin "6") (pinfunction "Q4_6") (pintype "input"))
      (node (ref "Q22") (pin "5") (pinfunction "A4_5") (pintype "input"))
      (node (ref "Q24") (pin "8") (pinfunction "D3_8") (pintype "input"))
      (node (ref "Q27") (pin "11") (pinfunction "4D_11") (pintype "input"))
      (node (ref "Q31") (pin "19") (pinfunction "A3P_19") (pintype "input"))
      (node (ref "Q35") (pin "5") (pinfunction "A4_5") (pintype "input"))
      (node (ref "Q36") (pin "8") (pinfunction "D3_8") (pintype "input"))
      (node (ref "Q36") (pin "9") (pinfunction "O3_9") (pintype "input"))
      (node (ref "Q38") (pin "9") (pinfunction "O3_9") (pintype "input"))
      (node (ref "Q42") (pin "8") (pinfunction "D3_8") (pintype "input"))
      (node (ref "Q6") (pin "3") (pinfunction "D4_3") (pintype "input"))
      (node (ref "Q6") (pin "6") (pinfunction "Q4_6") (pintype "input"))
    )
    (net (code "56") (name "/BUS 12") (class "Default")
      (node (ref "Q12") (pin "3") (pinfunction "P0_3") (pintype "input"))
      (node (ref "Q16") (pin "10") (pinfunction "Q1_10") (pintype "input"))
      (node (ref "Q16") (pin "15") (pinfunction "D1_15") (pintype "input"))
      (node (ref "Q22") (pin "6") (pinfunction "A5_6") (pintype "input"))
      (node (ref "Q24") (pin "13") (pinfunction "D4_13") (pintype "input"))
      (node (ref "Q26") (pin "14") (pinfunction "1D_14") (pintype "input"))
      (node (ref "Q30") (pin "2") (pinfunction "A0P_2") (pintype "input"))
      (node (ref "Q35") (pin "6") (pinfunction "A5_6") (pintype "input"))
      (node (ref "Q36") (pin "12") (pinfunction "O4_12") (pintype "input"))
      (node (ref "Q36") (pin "13") (pinfunction "D4_13") (pintype "input"))
      (node (ref "Q38") (pin "12") (pinfunction "O4_12") (pintype "input"))
      (node (ref "Q42") (pin "13") (pinfunction "D4_13") (pintype "input"))
      (node (ref "Q5") (pin "10") (pinfunction "Q1_10") (pintype "input"))
      (node (ref "Q5") (pin "15") (pinfunction "D1_15") (pintype "input"))
    )
    (net (code "57") (name "/BUS 13") (class "Default")
      (node (ref "Q12") (pin "4") (pinfunction "P1_4") (pintype "input"))
      (node (ref "Q16") (pin "1") (pinfunction "D2_1") (pintype "input"))
      (node (ref "Q16") (pin "9") (pinfunction "Q2_9") (pintype "input"))
      (node (ref "Q22") (pin "7") (pinfunction "A6_7") (pintype "input"))
      (node (ref "Q24") (pin "14") (pinfunction "D5_14") (pintype "input"))
      (node (ref "Q26") (pin "13") (pinfunction "2D_13") (pintype "input"))
      (node (ref "Q30") (pin "23") (pinfunction "A1P_23") (pintype "input"))
      (node (ref "Q35") (pin "7") (pinfunction "A6_7") (pintype "input"))
      (node (ref "Q36") (pin "14") (pinfunction "D5_14") (pintype "input"))
      (node (ref "Q36") (pin "15") (pinfunction "O5_15") (pintype "input"))
      (node (ref "Q38") (pin "15") (pinfunction "O5_15") (pintype "input"))
      (node (ref "Q42") (pin "14") (pinfunction "D5_14") (pintype "input"))
      (node (ref "Q5") (pin "1") (pinfunction "D2_1") (pintype "input"))
      (node (ref "Q5") (pin "9") (pinfunction "Q2_9") (pintype "input"))
    )
    (net (code "58") (name "/BUS 14") (class "Default")
      (node (ref "Q12") (pin "5") (pinfunction "P2_5") (pintype "input"))
      (node (ref "Q16") (pin "2") (pinfunction "D3_2") (pintype "input"))
      (node (ref "Q16") (pin "7") (pinfunction "Q3_7") (pintype "input"))
      (node (ref "Q22") (pin "8") (pinfunction "A7_8") (pintype "input"))
      (node (ref "Q24") (pin "17") (pinfunction "D6_17") (pintype "input"))
      (node (ref "Q26") (pin "12") (pinfunction "3D_12") (pintype "input"))
      (node (ref "Q30") (pin "21") (pinfunction "A2P_21") (pintype "input"))
      (node (ref "Q35") (pin "8") (pinfunction "A7_8") (pintype "input"))
      (node (ref "Q36") (pin "16") (pinfunction "O6_16") (pintype "input"))
      (node (ref "Q36") (pin "17") (pinfunction "D6_17") (pintype "input"))
      (node (ref "Q38") (pin "16") (pinfunction "O6_16") (pintype "input"))
      (node (ref "Q42") (pin "17") (pinfunction "D6_17") (pintype "input"))
      (node (ref "Q5") (pin "2") (pinfunction "D3_2") (pintype "input"))
      (node (ref "Q5") (pin "7") (pinfunction "Q3_7") (pintype "input"))
    )
    (net (code "59") (name "/BUS 15") (class "Default")
      (node (ref "Q12") (pin "6") (pinfunction "P3_6") (pintype "input"))
      (node (ref "Q16") (pin "3") (pinfunction "D4_3") (pintype "input"))
      (node (ref "Q16") (pin "6") (pinfunction "Q4_6") (pintype "input"))
      (node (ref "Q22") (pin "9") (pinfunction "A8_9") (pintype "input"))
      (node (ref "Q24") (pin "18") (pinfunction "D7_18") (pintype "input"))
      (node (ref "Q26") (pin "11") (pinfunction "4D_11") (pintype "input"))
      (node (ref "Q30") (pin "19") (pinfunction "A3P_19") (pintype "input"))
      (node (ref "Q35") (pin "9") (pinfunction "A8_9") (pintype "input"))
      (node (ref "Q36") (pin "18") (pinfunction "D7_18") (pintype "input"))
      (node (ref "Q36") (pin "19") (pinfunction "O7_19") (pintype "input"))
      (node (ref "Q38") (pin "19") (pinfunction "O7_19") (pintype "input"))
      (node (ref "Q42") (pin "18") (pinfunction "D7_18") (pintype "input"))
      (node (ref "Q5") (pin "3") (pinfunction "D4_3") (pintype "input"))
      (node (ref "Q5") (pin "6") (pinfunction "Q4_6") (pintype "input"))
    )
    (net (code "60") (name "/CLK") (class "Default")
      (node (ref "Q1") (pin "12") (pinfunction "A4_12") (pintype "input"))
      (node (ref "Q15") (pin "2") (pinfunction "CP_2") (pintype "input"))
      (node (ref "Q2") (pin "12") (pinfunction "A4_12") (pintype "input"))
      (node (ref "Q3") (pin "12") (pinfunction "A4_12") (pintype "input"))
    )
    (net (code "61") (name "/GATE PC") (class "Default")
      (node (ref "Q22") (pin "19") (pinfunction "(E)_19") (pintype "input"))
      (node (ref "Q23") (pin "19") (pinfunction "(E)_19") (pintype "input"))
    )
    (net (code "62") (name "/LED ALU 0") (class "Default")
      (node (ref "D49") (pin "1") (pinfunction "A_1") (pintype "passive"))
      (node (ref "Q41") (pin "2") (pinfunction "O0_2") (pintype "input"))
    )
    (net (code "63") (name "/LED ALU 1") (class "Default")
      (node (ref "D50") (pin "1") (pinfunction "A_1") (pintype "passive"))
      (node (ref "Q41") (pin "5") (pinfunction "O1_5") (pintype "input"))
    )
    (net (code "64") (name "/LED ALU 2") (class "Default")
      (node (ref "D51") (pin "1") (pinfunction "A_1") (pintype "passive"))
      (node (ref "Q41") (pin "6") (pinfunction "O2_6") (pintype "input"))
    )
    (net (code "65") (name "/LED ALU 3") (class "Default")
      (node (ref "D52") (pin "1") (pinfunction "A_1") (pintype "passive"))
      (node (ref "Q41") (pin "9") (pinfunction "O3_9") (pintype "input"))
    )
    (net (code "66") (name "/LED ALU 4") (class "Default")
      (node (ref "D53") (pin "1") (pinfunction "A_1") (pintype "passive"))
      (node (ref "Q41") (pin "12") (pinfunction "O4_12") (pintype "input"))
    )
    (net (code "67") (name "/LED ALU 5") (class "Default")
      (node (ref "D54") (pin "1") (pinfunction "A_1") (pintype "passive"))
      (node (ref "Q41") (pin "15") (pinfunction "O5_15") (pintype "input"))
    )
    (net (code "68") (name "/LED ALU 6") (class "Default")
      (node (ref "D55") (pin "1") (pinfunction "A_1") (pintype "passive"))
      (node (ref "Q41") (pin "16") (pinfunction "O6_16") (pintype "input"))
    )
    (net (code "69") (name "/LED ALU 7") (class "Default")
      (node (ref "D56") (pin "1") (pinfunction "A_1") (pintype "passive"))
      (node (ref "Q41") (pin "19") (pinfunction "O7_19") (pintype "input"))
    )
    (net (code "70") (name "/LED ALU 8") (class "Default")
      (node (ref "D57") (pin "1") (pinfunction "A_1") (pintype "passive"))
      (node (ref "Q40") (pin "2") (pinfunction "O0_2") (pintype "input"))
    )
    (net (code "71") (name "/LED ALU 9") (class "Default")
      (node (ref "D58") (pin "1") (pinfunction "A_1") (pintype "passive"))
      (node (ref "Q40") (pin "5") (pinfunction "O1_5") (pintype "input"))
    )
    (net (code "72") (name "/LED ALU 10") (class "Default")
      (node (ref "D59") (pin "1") (pinfunction "A_1") (pintype "passive"))
      (node (ref "Q40") (pin "6") (pinfunction "O2_6") (pintype "input"))
    )
    (net (code "73") (name "/LED ALU 11") (class "Default")
      (node (ref "D60") (pin "1") (pinfunction "A_1") (pintype "passive"))
      (node (ref "Q40") (pin "9") (pinfunction "O3_9") (pintype "input"))
    )
    (net (code "74") (name "/LED ALU 12") (class "Default")
      (node (ref "D61") (pin "1") (pinfunction "A_1") (pintype "passive"))
      (node (ref "Q40") (pin "12") (pinfunction "O4_12") (pintype "input"))
    )
    (net (code "75") (name "/LED ALU 13") (class "Default")
      (node (ref "D62") (pin "1") (pinfunction "A_1") (pintype "passive"))
      (node (ref "Q40") (pin "15") (pinfunction "O5_15") (pintype "input"))
    )
    (net (code "76") (name "/LED ALU 14") (class "Default")
      (node (ref "D63") (pin "1") (pinfunction "A_1") (pintype "passive"))
      (node (ref "Q40") (pin "16") (pinfunction "O6_16") (pintype "input"))
    )
    (net (code "77") (name "/LED ALU 15") (class "Default")
      (node (ref "D64") (pin "1") (pinfunction "A_1") (pintype "passive"))
      (node (ref "Q40") (pin "19") (pinfunction "O7_19") (pintype "input"))
    )
    (net (code "78") (name "/LED MDR 0") (class "Default")
      (node (ref "D33") (pin "1") (pinfunction "A_1") (pintype "passive"))
      (node (ref "Q43") (pin "2") (pinfunction "O0_2") (pintype "input"))
    )
    (net (code "79") (name "/LED MDR 1") (class "Default")
      (node (ref "D34") (pin "1") (pinfunction "A_1") (pintype "passive"))
      (node (ref "Q43") (pin "5") (pinfunction "O1_5") (pintype "input"))
    )
    (net (code "80") (name "/LED MDR 2") (class "Default")
      (node (ref "D35") (pin "1") (pinfunction "A_1") (pintype "passive"))
      (node (ref "Q43") (pin "6") (pinfunction "O2_6") (pintype "input"))
    )
    (net (code "81") (name "/LED MDR 3") (class "Default")
      (node (ref "D36") (pin "1") (pinfunction "A_1") (pintype "passive"))
      (node (ref "Q43") (pin "9") (pinfunction "O3_9") (pintype "input"))
    )
    (net (code "82") (name "/LED MDR 4") (class "Default")
      (node (ref "D37") (pin "1") (pinfunction "A_1") (pintype "passive"))
      (node (ref "Q43") (pin "12") (pinfunction "O4_12") (pintype "input"))
    )
    (net (code "83") (name "/LED MDR 5") (class "Default")
      (node (ref "D38") (pin "1") (pinfunction "A_1") (pintype "passive"))
      (node (ref "Q43") (pin "15") (pinfunction "O5_15") (pintype "input"))
    )
    (net (code "84") (name "/LED MDR 6") (class "Default")
      (node (ref "D39") (pin "1") (pinfunction "A_1") (pintype "passive"))
      (node (ref "Q43") (pin "16") (pinfunction "O6_16") (pintype "input"))
    )
    (net (code "85") (name "/LED MDR 7") (class "Default")
      (node (ref "D40") (pin "1") (pinfunction "A_1") (pintype "passive"))
      (node (ref "Q43") (pin "19") (pinfunction "O7_19") (pintype "input"))
    )
    (net (code "86") (name "/LED MDR 8") (class "Default")
      (node (ref "D41") (pin "1") (pinfunction "A_1") (pintype "passive"))
      (node (ref "Q42") (pin "2") (pinfunction "O0_2") (pintype "input"))
    )
    (net (code "87") (name "/LED MDR 9") (class "Default")
      (node (ref "D42") (pin "1") (pinfunction "A_1") (pintype "passive"))
      (node (ref "Q42") (pin "5") (pinfunction "O1_5") (pintype "input"))
    )
    (net (code "88") (name "/LED MDR 10") (class "Default")
      (node (ref "D43") (pin "1") (pinfunction "A_1") (pintype "passive"))
      (node (ref "Q42") (pin "6") (pinfunction "O2_6") (pintype "input"))
    )
    (net (code "89") (name "/LED MDR 11") (class "Default")
      (node (ref "D44") (pin "1") (pinfunction "A_1") (pintype "passive"))
      (node (ref "Q42") (pin "9") (pinfunction "O3_9") (pintype "input"))
    )
    (net (code "90") (name "/LED MDR 12") (class "Default")
      (node (ref "D45") (pin "1") (pinfunction "A_1") (pintype "passive"))
      (node (ref "Q42") (pin "12") (pinfunction "O4_12") (pintype "input"))
    )
    (net (code "91") (name "/LED MDR 13") (class "Default")
      (node (ref "D46") (pin "1") (pinfunction "A_1") (pintype "passive"))
      (node (ref "Q42") (pin "15") (pinfunction "O5_15") (pintype "input"))
    )
    (net (code "92") (name "/LED MDR 14") (class "Default")
      (node (ref "D47") (pin "1") (pinfunction "A_1") (pintype "passive"))
      (node (ref "Q42") (pin "16") (pinfunction "O6_16") (pintype "input"))
    )
    (net (code "93") (name "/LED MDR 15") (class "Default")
      (node (ref "D48") (pin "1") (pinfunction "A_1") (pintype "passive"))
      (node (ref "Q42") (pin "19") (pinfunction "O7_19") (pintype "input"))
    )
    (net (code "94") (name "/LED PC 0") (class "Default")
      (node (ref "D1") (pin "2") (pinfunction "K_2") (pintype "passive"))
      (node (ref "Q15") (pin "14") (pinfunction "Q0_14") (pintype "input"))
      (node (ref "Q23") (pin "18") (pinfunction "B1_18") (pintype "input"))
    )
    (net (code "95") (name "/LED PC 1") (class "Default")
      (node (ref "D2") (pin "2") (pinfunction "K_2") (pintype "passive"))
      (node (ref "Q15") (pin "13") (pinfunction "Q1_13") (pintype "input"))
      (node (ref "Q23") (pin "17") (pinfunction "B2_17") (pintype "input"))
    )
    (net (code "96") (name "/LED PC 2") (class "Default")
      (node (ref "D3") (pin "2") (pinfunction "K_2") (pintype "passive"))
      (node (ref "Q15") (pin "12") (pinfunction "Q2_12") (pintype "input"))
      (node (ref "Q23") (pin "16") (pinfunction "B3_16") (pintype "input"))
    )
    (net (code "97") (name "/LED PC 3") (class "Default")
      (node (ref "D4") (pin "2") (pinfunction "K_2") (pintype "passive"))
      (node (ref "Q15") (pin "11") (pinfunction "Q3_11") (pintype "input"))
      (node (ref "Q23") (pin "15") (pinfunction "B4_15") (pintype "input"))
    )
    (net (code "98") (name "/LED PC 4") (class "Default")
      (node (ref "D5") (pin "2") (pinfunction "K_2") (pintype "passive"))
      (node (ref "Q14") (pin "14") (pinfunction "Q0_14") (pintype "input"))
      (node (ref "Q23") (pin "14") (pinfunction "B5_14") (pintype "input"))
    )
    (net (code "99") (name "/LED PC 5") (class "Default")
      (node (ref "D6") (pin "2") (pinfunction "K_2") (pintype "passive"))
      (node (ref "Q14") (pin "13") (pinfunction "Q1_13") (pintype "input"))
      (node (ref "Q23") (pin "13") (pinfunction "B6_13") (pintype "input"))
    )
    (net (code "100") (name "/LED PC 6") (class "Default")
      (node (ref "D7") (pin "2") (pinfunction "K_2") (pintype "passive"))
      (node (ref "Q14") (pin "12") (pinfunction "Q2_12") (pintype "input"))
      (node (ref "Q23") (pin "12") (pinfunction "B7_12") (pintype "input"))
    )
    (net (code "101") (name "/LED PC 7") (class "Default")
      (node (ref "D8") (pin "2") (pinfunction "K_2") (pintype "passive"))
      (node (ref "Q14") (pin "11") (pinfunction "Q3_11") (pintype "input"))
      (node (ref "Q23") (pin "11") (pinfunction "B8_11") (pintype "input"))
    )
    (net (code "102") (name "/LED PC 8") (class "Default")
      (node (ref "D9") (pin "2") (pinfunction "K_2") (pintype "passive"))
      (node (ref "Q13") (pin "14") (pinfunction "Q0_14") (pintype "input"))
      (node (ref "Q22") (pin "18") (pinfunction "B1_18") (pintype "input"))
    )
    (net (code "103") (name "/LED PC 9") (class "Default")
      (node (ref "D10") (pin "2") (pinfunction "K_2") (pintype "passive"))
      (node (ref "Q13") (pin "13") (pinfunction "Q1_13") (pintype "input"))
      (node (ref "Q22") (pin "17") (pinfunction "B2_17") (pintype "input"))
    )
    (net (code "104") (name "/LED PC 10") (class "Default")
      (node (ref "D11") (pin "2") (pinfunction "K_2") (pintype "passive"))
      (node (ref "Q13") (pin "12") (pinfunction "Q2_12") (pintype "input"))
      (node (ref "Q22") (pin "16") (pinfunction "B3_16") (pintype "input"))
    )
    (net (code "105") (name "/LED PC 11") (class "Default")
      (node (ref "D12") (pin "2") (pinfunction "K_2") (pintype "passive"))
      (node (ref "Q13") (pin "11") (pinfunction "Q3_11") (pintype "input"))
      (node (ref "Q22") (pin "15") (pinfunction "B4_15") (pintype "input"))
    )
    (net (code "106") (name "/LED PC 12") (class "Default")
      (node (ref "D13") (pin "2") (pinfunction "K_2") (pintype "passive"))
      (node (ref "Q12") (pin "14") (pinfunction "Q0_14") (pintype "input"))
      (node (ref "Q22") (pin "14") (pinfunction "B5_14") (pintype "input"))
    )
    (net (code "107") (name "/LED PC 13") (class "Default")
      (node (ref "D14") (pin "2") (pinfunction "K_2") (pintype "passive"))
      (node (ref "Q12") (pin "13") (pinfunction "Q1_13") (pintype "input"))
      (node (ref "Q22") (pin "13") (pinfunction "B6_13") (pintype "input"))
    )
    (net (code "108") (name "/LED PC 14") (class "Default")
      (node (ref "D15") (pin "2") (pinfunction "K_2") (pintype "passive"))
      (node (ref "Q12") (pin "12") (pinfunction "Q2_12") (pintype "input"))
      (node (ref "Q22") (pin "12") (pinfunction "B7_12") (pintype "input"))
    )
    (net (code "109") (name "/LED PC 15") (class "Default")
      (node (ref "D16") (pin "2") (pinfunction "K_2") (pintype "passive"))
      (node (ref "Q12") (pin "11") (pinfunction "Q3_11") (pintype "input"))
      (node (ref "Q22") (pin "11") (pinfunction "B8_11") (pintype "input"))
    )
    (net (code "110") (name "/MAR 0") (class "Default")
      (node (ref "Q29") (pin "3") (pinfunction "1Q_3") (pintype "input"))
      (node (ref "Q34") (pin "12") (pinfunction "A0_12") (pintype "input"))
    )
    (net (code "111") (name "/MAR 1") (class "Default")
      (node (ref "Q29") (pin "4") (pinfunction "2Q_4") (pintype "input"))
      (node (ref "Q34") (pin "11") (pinfunction "A1_11") (pintype "input"))
    )
    (net (code "112") (name "/MAR 2") (class "Default")
      (node (ref "Q29") (pin "5") (pinfunction "3Q_5") (pintype "input"))
      (node (ref "Q34") (pin "10") (pinfunction "A2_10") (pintype "input"))
    )
    (net (code "113") (name "/MAR 3") (class "Default")
      (node (ref "Q29") (pin "6") (pinfunction "4Q_6") (pintype "input"))
      (node (ref "Q34") (pin "9") (pinfunction "A3_9") (pintype "input"))
    )
    (net (code "114") (name "/MAR 4") (class "Default")
      (node (ref "Q28") (pin "3") (pinfunction "1Q_3") (pintype "input"))
      (node (ref "Q34") (pin "8") (pinfunction "A4_8") (pintype "input"))
    )
    (net (code "115") (name "/MAR 5") (class "Default")
      (node (ref "Q28") (pin "4") (pinfunction "2Q_4") (pintype "input"))
      (node (ref "Q34") (pin "7") (pinfunction "A5_7") (pintype "input"))
    )
    (net (code "116") (name "/MAR 6") (class "Default")
      (node (ref "Q28") (pin "5") (pinfunction "3Q_5") (pintype "input"))
      (node (ref "Q34") (pin "6") (pinfunction "A6_6") (pintype "input"))
    )
    (net (code "117") (name "/MAR 7") (class "Default")
      (node (ref "Q28") (pin "6") (pinfunction "4Q_6") (pintype "input"))
      (node (ref "Q34") (pin "5") (pinfunction "A7_5") (pintype "input"))
    )
    (net (code "118") (name "/MAR 8") (class "Default")
      (node (ref "Q27") (pin "3") (pinfunction "1Q_3") (pintype "input"))
      (node (ref "Q34") (pin "27") (pinfunction "A8_27") (pintype "input"))
    )
    (net (code "119") (name "/MAR 9") (class "Default")
      (node (ref "Q27") (pin "4") (pinfunction "2Q_4") (pintype "input"))
      (node (ref "Q34") (pin "26") (pinfunction "A9_26") (pintype "input"))
    )
    (net (code "120") (name "/MAR 10") (class "Default")
      (node (ref "Q27") (pin "5") (pinfunction "3Q_5") (pintype "input"))
      (node (ref "Q34") (pin "23") (pinfunction "A10_23") (pintype "input"))
    )
    (net (code "121") (name "/MAR 11") (class "Default")
      (node (ref "Q27") (pin "6") (pinfunction "4Q_6") (pintype "input"))
      (node (ref "Q34") (pin "25") (pinfunction "A11_25") (pintype "input"))
    )
    (net (code "122") (name "/MAR 12") (class "Default")
      (node (ref "Q26") (pin "3") (pinfunction "1Q_3") (pintype "input"))
      (node (ref "Q34") (pin "4") (pinfunction "A12_4") (pintype "input"))
    )
    (net (code "123") (name "/MAR 13") (class "Default")
      (node (ref "Q26") (pin "4") (pinfunction "2Q_4") (pintype "input"))
      (node (ref "Q34") (pin "28") (pinfunction "A13_28") (pintype "input"))
    )
    (net (code "124") (name "/MAR 14") (class "Default")
      (node (ref "Q26") (pin "5") (pinfunction "3Q_5") (pintype "input"))
      (node (ref "Q34") (pin "3") (pinfunction "A14_3") (pintype "input"))
    )
    (net (code "125") (name "/MAR 15") (class "Default")
      (node (ref "Q26") (pin "6") (pinfunction "4Q_6") (pintype "input"))
      (node (ref "Q34") (pin "31") (pinfunction "A15_31") (pintype "input"))
    )
    (net (code "126") (name "/MDR R") (class "Default")
      (node (ref "Q36") (pin "1") (pinfunction "OE_1") (pintype "input"))
      (node (ref "Q37") (pin "1") (pinfunction "OE_1") (pintype "input"))
    )
    (net (code "127") (name "/MDR W") (class "Default")
      (node (ref "Q36") (pin "11") (pinfunction "LE_11") (pintype "input"))
      (node (ref "Q37") (pin "11") (pinfunction "LE_11") (pintype "input"))
      (node (ref "Q42") (pin "11") (pinfunction "LE_11") (pintype "input"))
      (node (ref "Q43") (pin "11") (pinfunction "LE_11") (pintype "input"))
    )
    (net (code "128") (name "/MEM R") (class "Default")
      (node (ref "Q34") (pin "24") (pinfunction "(OE)_24") (pintype "input"))
    )
    (net (code "129") (name "/MEM W") (class "Default")
      (node (ref "Q34") (pin "29") (pinfunction "(WE)_29") (pintype "input"))
    )
    (net (code "130") (name "/PC EN") (class "Default")
      (node (ref "Q12") (pin "10") (pinfunction "CET_10") (pintype "input"))
      (node (ref "Q13") (pin "10") (pinfunction "CET_10") (pintype "input"))
      (node (ref "Q14") (pin "10") (pinfunction "CET_10") (pintype "input"))
      (node (ref "Q15") (pin "10") (pinfunction "CET_10") (pintype "input"))
    )
    (net (code "131") (name "/PC RST") (class "Default")
      (node (ref "Q12") (pin "1") (pinfunction "*R_1") (pintype "input"))
      (node (ref "Q13") (pin "1") (pinfunction "*R_1") (pintype "input"))
      (node (ref "Q14") (pin "1") (pinfunction "*R_1") (pintype "input"))
      (node (ref "Q15") (pin "1") (pinfunction "*R_1") (pintype "input"))
      (node (ref "Q4") (pin "12") (pinfunction "Y6_12") (pintype "input"))
    )
    (net (code "132") (name "/PC RST SW") (class "Default")
      (node (ref "Q4") (pin "13") (pinfunction "A6_13") (pintype "input"))
    )
    (net (code "133") (name "/PC SET") (class "Default")
      (node (ref "Q1") (pin "5") (pinfunction "B2_5") (pintype "input"))
      (node (ref "Q12") (pin "9") (pinfunction "(PE)_9") (pintype "input"))
      (node (ref "Q13") (pin "9") (pinfunction "(PE)_9") (pintype "input"))
      (node (ref "Q14") (pin "9") (pinfunction "(PE)_9") (pintype "input"))
      (node (ref "Q15") (pin "9") (pinfunction "(PE)_9") (pintype "input"))
      (node (ref "Q2") (pin "5") (pinfunction "B2_5") (pintype "input"))
      (node (ref "Q3") (pin "5") (pinfunction "B2_5") (pintype "input"))
      (node (ref "Q4") (pin "1") (pinfunction "A1_1") (pintype "input"))
    )
    (net (code "134") (name "/RF BOT READ") (class "Default")
      (node (ref "Q16") (pin "11") (pinfunction "(GR)_11") (pintype "input"))
      (node (ref "Q17") (pin "11") (pinfunction "(GR)_11") (pintype "input"))
      (node (ref "Q18") (pin "11") (pinfunction "(GR)_11") (pintype "input"))
      (node (ref "Q19") (pin "11") (pinfunction "(GR)_11") (pintype "input"))
      (node (ref "Q20") (pin "11") (pinfunction "Y4_11") (pintype "input"))
    )
    (net (code "135") (name "/RF BOT WR") (class "Default")
      (node (ref "Q16") (pin "12") (pinfunction "(GW)_12") (pintype "input"))
      (node (ref "Q17") (pin "12") (pinfunction "(GW)_12") (pintype "input"))
      (node (ref "Q18") (pin "12") (pinfunction "(GW)_12") (pintype "input"))
      (node (ref "Q19") (pin "12") (pinfunction "(GW)_12") (pintype "input"))
      (node (ref "Q21") (pin "11") (pinfunction "Y4_11") (pintype "input"))
    )
    (net (code "136") (name "/RF R") (class "Default")
      (node (ref "Q11") (pin "1") (pinfunction "A1_1") (pintype "input"))
      (node (ref "Q20") (pin "2") (pinfunction "B1_2") (pintype "input"))
      (node (ref "Q9") (pin "1") (pinfunction "A1_1") (pintype "input"))
    )
    (net (code "137") (name "/RF R0") (class "Default")
      (node (ref "Q16") (pin "14") (pinfunction "WA_14") (pintype "input"))
      (node (ref "Q16") (pin "5") (pinfunction "RA_5") (pintype "input"))
      (node (ref "Q17") (pin "14") (pinfunction "WA_14") (pintype "input"))
      (node (ref "Q17") (pin "5") (pinfunction "RA_5") (pintype "input"))
      (node (ref "Q18") (pin "14") (pinfunction "WA_14") (pintype "input"))
      (node (ref "Q18") (pin "5") (pinfunction "RA_5") (pintype "input"))
      (node (ref "Q19") (pin "14") (pinfunction "WA_14") (pintype "input"))
      (node (ref "Q19") (pin "5") (pinfunction "RA_5") (pintype "input"))
      (node (ref "Q5") (pin "14") (pinfunction "WA_14") (pintype "input"))
      (node (ref "Q5") (pin "5") (pinfunction "RA_5") (pintype "input"))
      (node (ref "Q6") (pin "14") (pinfunction "WA_14") (pintype "input"))
      (node (ref "Q6") (pin "5") (pinfunction "RA_5") (pintype "input"))
      (node (ref "Q7") (pin "14") (pinfunction "WA_14") (pintype "input"))
      (node (ref "Q7") (pin "5") (pinfunction "RA_5") (pintype "input"))
      (node (ref "Q8") (pin "14") (pinfunction "WA_14") (pintype "input"))
      (node (ref "Q8") (pin "5") (pinfunction "RA_5") (pintype "input"))
    )
    (net (code "138") (name "/RF R1") (class "Default")
      (node (ref "Q16") (pin "13") (pinfunction "WB_13") (pintype "input"))
      (node (ref "Q16") (pin "4") (pinfunction "RB_4") (pintype "input"))
      (node (ref "Q17") (pin "13") (pinfunction "WB_13") (pintype "input"))
      (node (ref "Q17") (pin "4") (pinfunction "RB_4") (pintype "input"))
      (node (ref "Q18") (pin "13") (pinfunction "WB_13") (pintype "input"))
      (node (ref "Q18") (pin "4") (pinfunction "RB_4") (pintype "input"))
      (node (ref "Q19") (pin "13") (pinfunction "WB_13") (pintype "input"))
      (node (ref "Q19") (pin "4") (pinfunction "RB_4") (pintype "input"))
      (node (ref "Q5") (pin "13") (pinfunction "WB_13") (pintype "input"))
      (node (ref "Q5") (pin "4") (pinfunction "RB_4") (pintype "input"))
      (node (ref "Q6") (pin "13") (pinfunction "WB_13") (pintype "input"))
      (node (ref "Q6") (pin "4") (pinfunction "RB_4") (pintype "input"))
      (node (ref "Q7") (pin "13") (pinfunction "WB_13") (pintype "input"))
      (node (ref "Q7") (pin "4") (pinfunction "RB_4") (pintype "input"))
      (node (ref "Q8") (pin "13") (pinfunction "WB_13") (pintype "input"))
      (node (ref "Q8") (pin "4") (pinfunction "RB_4") (pintype "input"))
    )
    (net (code "139") (name "/RF R2") (class "Default")
      (node (ref "Q11") (pin "5") (pinfunction "A3_5") (pintype "input"))
      (node (ref "Q20") (pin "1") (pinfunction "A1_1") (pintype "input"))
      (node (ref "Q21") (pin "1") (pinfunction "A1_1") (pintype "input"))
    )
    (net (code "140") (name "/RF R2P") (class "Default")
      (node (ref "Q10") (pin "13") (pinfunction "B4_13") (pintype "input"))
      (node (ref "Q11") (pin "6") (pinfunction "Y3_6") (pintype "input"))
      (node (ref "Q21") (pin "13") (pinfunction "B4_13") (pintype "input"))
      (node (ref "Q9") (pin "13") (pinfunction "B4_13") (pintype "input"))
    )
    (net (code "141") (name "/RF RP") (class "Default")
      (node (ref "Q10") (pin "2") (pinfunction "B1_2") (pintype "input"))
      (node (ref "Q11") (pin "2") (pinfunction "Y1_2") (pintype "input"))
    )
    (net (code "142") (name "/RF TOP READ") (class "Default")
      (node (ref "Q5") (pin "11") (pinfunction "(GR)_11") (pintype "input"))
      (node (ref "Q6") (pin "11") (pinfunction "(GR)_11") (pintype "input"))
      (node (ref "Q7") (pin "11") (pinfunction "(GR)_11") (pintype "input"))
      (node (ref "Q8") (pin "11") (pinfunction "(GR)_11") (pintype "input"))
      (node (ref "Q9") (pin "11") (pinfunction "Y4_11") (pintype "input"))
    )
    (net (code "143") (name "/RF TOP WR") (class "Default")
      (node (ref "Q10") (pin "11") (pinfunction "Y4_11") (pintype "input"))
      (node (ref "Q5") (pin "12") (pinfunction "(GW)_12") (pintype "input"))
      (node (ref "Q6") (pin "12") (pinfunction "(GW)_12") (pintype "input"))
      (node (ref "Q7") (pin "12") (pinfunction "(GW)_12") (pintype "input"))
      (node (ref "Q8") (pin "12") (pinfunction "(GW)_12") (pintype "input"))
    )
    (net (code "144") (name "/RF W") (class "Default")
      (node (ref "Q10") (pin "1") (pinfunction "A1_1") (pintype "input"))
      (node (ref "Q11") (pin "3") (pinfunction "A2_3") (pintype "input"))
      (node (ref "Q21") (pin "2") (pinfunction "B1_2") (pintype "input"))
    )
    (net (code "145") (name "/RF WP") (class "Default")
      (node (ref "Q11") (pin "4") (pinfunction "Y2_4") (pintype "input"))
      (node (ref "Q20") (pin "13") (pinfunction "B4_13") (pintype "input"))
      (node (ref "Q9") (pin "2") (pinfunction "B1_2") (pintype "input"))
    )
    (net (code "146") (name "/SW PC") (class "Default")
      (node (ref "Q1") (pin "13") (pinfunction "B4_13") (pintype "input"))
      (node (ref "Q2") (pin "13") (pinfunction "B4_13") (pintype "input"))
    )
    (net (code "147") (name "GND") (class "Default")
      (node (ref "D17") (pin "2") (pinfunction "K_2") (pintype "passive"))
      (node (ref "D18") (pin "2") (pinfunction "K_2") (pintype "passive"))
      (node (ref "D19") (pin "2") (pinfunction "K_2") (pintype "passive"))
      (node (ref "D20") (pin "2") (pinfunction "K_2") (pintype "passive"))
      (node (ref "D21") (pin "2") (pinfunction "K_2") (pintype "passive"))
      (node (ref "D22") (pin "2") (pinfunction "K_2") (pintype "passive"))
      (node (ref "D23") (pin "2") (pinfunction "K_2") (pintype "passive"))
      (node (ref "D24") (pin "2") (pinfunction "K_2") (pintype "passive"))
      (node (ref "D25") (pin "2") (pinfunction "K_2") (pintype "passive"))
      (node (ref "D26") (pin "2") (pinfunction "K_2") (pintype "passive"))
      (node (ref "D27") (pin "2") (pinfunction "K_2") (pintype "passive"))
      (node (ref "D28") (pin "2") (pinfunction "K_2") (pintype "passive"))
      (node (ref "D29") (pin "2") (pinfunction "K_2") (pintype "passive"))
      (node (ref "D30") (pin "2") (pinfunction "K_2") (pintype "passive"))
      (node (ref "D31") (pin "2") (pinfunction "K_2") (pintype "passive"))
      (node (ref "D32") (pin "2") (pinfunction "K_2") (pintype "passive"))
      (node (ref "D49") (pin "2") (pinfunction "K_2") (pintype "passive"))
      (node (ref "D50") (pin "2") (pinfunction "K_2") (pintype "passive"))
      (node (ref "D51") (pin "2") (pinfunction "K_2") (pintype "passive"))
      (node (ref "D52") (pin "2") (pinfunction "K_2") (pintype "passive"))
      (node (ref "D53") (pin "2") (pinfunction "K_2") (pintype "passive"))
      (node (ref "D54") (pin "2") (pinfunction "K_2") (pintype "passive"))
      (node (ref "D55") (pin "2") (pinfunction "K_2") (pintype "passive"))
      (node (ref "D56") (pin "2") (pinfunction "K_2") (pintype "passive"))
      (node (ref "D57") (pin "2") (pinfunction "K_2") (pintype "passive"))
      (node (ref "D58") (pin "2") (pinfunction "K_2") (pintype "passive"))
      (node (ref "D59") (pin "2") (pinfunction "K_2") (pintype "passive"))
      (node (ref "D60") (pin "2") (pinfunction "K_2") (pintype "passive"))
      (node (ref "D61") (pin "2") (pinfunction "K_2") (pintype "passive"))
      (node (ref "D62") (pin "2") (pinfunction "K_2") (pintype "passive"))
      (node (ref "D63") (pin "2") (pinfunction "K_2") (pintype "passive"))
      (node (ref "D64") (pin "2") (pinfunction "K_2") (pintype "passive"))
      (node (ref "Q1") (pin "7") (pinfunction "GND_7") (pintype "input"))
      (node (ref "Q10") (pin "7") (pinfunction "GND_7") (pintype "input"))
      (node (ref "Q11") (pin "7") (pinfunction "GND_7") (pintype "input"))
      (node (ref "Q12") (pin "8") (pinfunction "GND_8") (pintype "input"))
      (node (ref "Q13") (pin "8") (pinfunction "GND_8") (pintype "input"))
      (node (ref "Q14") (pin "8") (pinfunction "GND_8") (pintype "input"))
      (node (ref "Q15") (pin "8") (pinfunction "GND_8") (pintype "input"))
      (node (ref "Q16") (pin "8") (pinfunction "GND_8") (pintype "input"))
      (node (ref "Q17") (pin "8") (pinfunction "GND_8") (pintype "input"))
      (node (ref "Q18") (pin "8") (pinfunction "GND_8") (pintype "input"))
      (node (ref "Q19") (pin "8") (pinfunction "GND_8") (pintype "input"))
      (node (ref "Q2") (pin "7") (pinfunction "GND_7") (pintype "input"))
      (node (ref "Q20") (pin "7") (pinfunction "GND_7") (pintype "input"))
      (node (ref "Q21") (pin "7") (pinfunction "GND_7") (pintype "input"))
      (node (ref "Q22") (pin "1") (pinfunction "DIR_1") (pintype "input"))
      (node (ref "Q22") (pin "10") (pinfunction "GND_10") (pintype "input"))
      (node (ref "Q23") (pin "1") (pinfunction "DIR_1") (pintype "input"))
      (node (ref "Q23") (pin "10") (pinfunction "GND_10") (pintype "input"))
      (node (ref "Q24") (pin "1") (pinfunction "OE_1") (pintype "input"))
      (node (ref "Q24") (pin "10") (pinfunction "GND_10") (pintype "input"))
      (node (ref "Q25") (pin "1") (pinfunction "OE_1") (pintype "input"))
      (node (ref "Q26") (pin "1") (pinfunction "M_1") (pintype "input"))
      (node (ref "Q26") (pin "15") (pinfunction "CLR_15") (pintype "input"))
      (node (ref "Q26") (pin "2") (pinfunction "N_2") (pintype "input"))
      (node (ref "Q26") (pin "8") (pinfunction "GND_8") (pintype "input"))
      (node (ref "Q27") (pin "1") (pinfunction "M_1") (pintype "input"))
      (node (ref "Q27") (pin "15") (pinfunction "CLR_15") (pintype "input"))
      (node (ref "Q27") (pin "2") (pinfunction "N_2") (pintype "input"))
      (node (ref "Q27") (pin "8") (pinfunction "GND_8") (pintype "input"))
      (node (ref "Q28") (pin "1") (pinfunction "M_1") (pintype "input"))
      (node (ref "Q28") (pin "15") (pinfunction "CLR_15") (pintype "input"))
      (node (ref "Q28") (pin "2") (pinfunction "N_2") (pintype "input"))
      (node (ref "Q28") (pin "8") (pinfunction "GND_8") (pintype "input"))
      (node (ref "Q29") (pin "1") (pinfunction "M_1") (pintype "input"))
      (node (ref "Q29") (pin "15") (pinfunction "CLR_15") (pintype "input"))
      (node (ref "Q29") (pin "2") (pinfunction "N_2") (pintype "input"))
      (node (ref "Q29") (pin "8") (pinfunction "GND_8") (pintype "input"))
      (node (ref "Q3") (pin "7") (pinfunction "GND_7") (pintype "input"))
      (node (ref "Q30") (pin "12") (pinfunction "GND_12") (pintype "input"))
      (node (ref "Q31") (pin "12") (pinfunction "GND_12") (pintype "input"))
      (node (ref "Q32") (pin "12") (pinfunction "GND_12") (pintype "input"))
      (node (ref "Q33") (pin "12") (pinfunction "GND_12") (pintype "input"))
      (node (ref "Q34") (pin "1") (pinfunction "NC_1") (pintype "input"))
      (node (ref "Q34") (pin "16") (pinfunction "GND_16") (pintype "input"))
      (node (ref "Q34") (pin "2") (pinfunction "NC_2") (pintype "input"))
      (node (ref "Q34") (pin "22") (pinfunction "(CE1)_22") (pintype "input"))
      (node (ref "Q35") (pin "10") (pinfunction "GND_10") (pintype "input"))
      (node (ref "Q36") (pin "10") (pinfunction "GND_10") (pintype "input"))
      (node (ref "Q37") (pin "10") (pinfunction "GND_10") (pintype "input"))
      (node (ref "Q38") (pin "10") (pinfunction "GND_10") (pintype "input"))
      (node (ref "Q39") (pin "10") (pinfunction "GND_10") (pintype "input"))
      (node (ref "Q4") (pin "7") (pinfunction "GND_7") (pintype "input"))
      (node (ref "Q40") (pin "1") (pinfunction "OE_1") (pintype "input"))
      (node (ref "Q40") (pin "10") (pinfunction "GND_10") (pintype "input"))
      (node (ref "Q41") (pin "1") (pinfunction "OE_1") (pintype "input"))
      (node (ref "Q41") (pin "10") (pinfunction "GND_10") (pintype "input"))
      (node (ref "Q42") (pin "1") (pinfunction "OE_1") (pintype "input"))
      (node (ref "Q42") (pin "10") (pinfunction "GND_10") (pintype "input"))
      (node (ref "Q43") (pin "1") (pinfunction "OE_1") (pintype "input"))
      (node (ref "Q43") (pin "10") (pinfunction "GND_10") (pintype "input"))
      (node (ref "Q5") (pin "8") (pinfunction "GND_8") (pintype "input"))
      (node (ref "Q6") (pin "8") (pinfunction "GND_8") (pintype "input"))
      (node (ref "Q7") (pin "8") (pinfunction "GND_8") (pintype "input"))
      (node (ref "Q8") (pin "8") (pinfunction "GND_8") (pintype "input"))
      (node (ref "Q9") (pin "7") (pinfunction "GND_7") (pintype "input"))
      (node (ref "R1") (pin "1") (pinfunction "1_1") (pintype "passive"))
      (node (ref "R10") (pin "1") (pinfunction "1_1") (pintype "passive"))
      (node (ref "R11") (pin "1") (pinfunction "1_1") (pintype "passive"))
      (node (ref "R12") (pin "1") (pinfunction "1_1") (pintype "passive"))
      (node (ref "R13") (pin "1") (pinfunction "1_1") (pintype "passive"))
      (node (ref "R14") (pin "1") (pinfunction "1_1") (pintype "passive"))
      (node (ref "R15") (pin "1") (pinfunction "1_1") (pintype "passive"))
      (node (ref "R16") (pin "1") (pinfunction "1_1") (pintype "passive"))
      (node (ref "R2") (pin "1") (pinfunction "1_1") (pintype "passive"))
      (node (ref "R3") (pin "1") (pinfunction "1_1") (pintype "passive"))
      (node (ref "R4") (pin "1") (pinfunction "1_1") (pintype "passive"))
      (node (ref "R5") (pin "1") (pinfunction "1_1") (pintype "passive"))
      (node (ref "R6") (pin "1") (pinfunction "1_1") (pintype "passive"))
      (node (ref "R7") (pin "1") (pinfunction "1_1") (pintype "passive"))
      (node (ref "R8") (pin "1") (pinfunction "1_1") (pintype "passive"))
      (node (ref "R9") (pin "1") (pinfunction "1_1") (pintype "passive"))
    )
    (net (code "148") (name "Net-(D33-K)") (class "Default")
      (node (ref "D33") (pin "2") (pinfunction "K_2") (pintype "passive"))
      (node (ref "R1") (pin "2") (pinfunction "2_2") (pintype "passive"))
    )
    (net (code "149") (name "Net-(D34-K)") (class "Default")
      (node (ref "D34") (pin "2") (pinfunction "K_2") (pintype "passive"))
      (node (ref "R2") (pin "2") (pinfunction "2_2") (pintype "passive"))
    )
    (net (code "150") (name "Net-(D35-K)") (class "Default")
      (node (ref "D35") (pin "2") (pinfunction "K_2") (pintype "passive"))
      (node (ref "R3") (pin "2") (pinfunction "2_2") (pintype "passive"))
    )
    (net (code "151") (name "Net-(D36-K)") (class "Default")
      (node (ref "D36") (pin "2") (pinfunction "K_2") (pintype "passive"))
      (node (ref "R4") (pin "2") (pinfunction "2_2") (pintype "passive"))
    )
    (net (code "152") (name "Net-(D37-K)") (class "Default")
      (node (ref "D37") (pin "2") (pinfunction "K_2") (pintype "passive"))
      (node (ref "R5") (pin "2") (pinfunction "2_2") (pintype "passive"))
    )
    (net (code "153") (name "Net-(D38-K)") (class "Default")
      (node (ref "D38") (pin "2") (pinfunction "K_2") (pintype "passive"))
      (node (ref "R6") (pin "2") (pinfunction "2_2") (pintype "passive"))
    )
    (net (code "154") (name "Net-(D39-K)") (class "Default")
      (node (ref "D39") (pin "2") (pinfunction "K_2") (pintype "passive"))
      (node (ref "R7") (pin "2") (pinfunction "2_2") (pintype "passive"))
    )
    (net (code "155") (name "Net-(D40-K)") (class "Default")
      (node (ref "D40") (pin "2") (pinfunction "K_2") (pintype "passive"))
      (node (ref "R8") (pin "2") (pinfunction "2_2") (pintype "passive"))
    )
    (net (code "156") (name "Net-(D41-K)") (class "Default")
      (node (ref "D41") (pin "2") (pinfunction "K_2") (pintype "passive"))
      (node (ref "R9") (pin "2") (pinfunction "2_2") (pintype "passive"))
    )
    (net (code "157") (name "Net-(D42-K)") (class "Default")
      (node (ref "D42") (pin "2") (pinfunction "K_2") (pintype "passive"))
      (node (ref "R10") (pin "2") (pinfunction "2_2") (pintype "passive"))
    )
    (net (code "158") (name "Net-(D43-K)") (class "Default")
      (node (ref "D43") (pin "2") (pinfunction "K_2") (pintype "passive"))
      (node (ref "R11") (pin "2") (pinfunction "2_2") (pintype "passive"))
    )
    (net (code "159") (name "Net-(D44-K)") (class "Default")
      (node (ref "D44") (pin "2") (pinfunction "K_2") (pintype "passive"))
      (node (ref "R12") (pin "2") (pinfunction "2_2") (pintype "passive"))
    )
    (net (code "160") (name "Net-(D45-K)") (class "Default")
      (node (ref "D45") (pin "2") (pinfunction "K_2") (pintype "passive"))
      (node (ref "R13") (pin "2") (pinfunction "2_2") (pintype "passive"))
    )
    (net (code "161") (name "Net-(D46-K)") (class "Default")
      (node (ref "D46") (pin "2") (pinfunction "K_2") (pintype "passive"))
      (node (ref "R14") (pin "2") (pinfunction "2_2") (pintype "passive"))
    )
    (net (code "162") (name "Net-(D47-K)") (class "Default")
      (node (ref "D47") (pin "2") (pinfunction "K_2") (pintype "passive"))
      (node (ref "R15") (pin "2") (pinfunction "2_2") (pintype "passive"))
    )
    (net (code "163") (name "Net-(D48-K)") (class "Default")
      (node (ref "D48") (pin "2") (pinfunction "K_2") (pintype "passive"))
      (node (ref "R16") (pin "2") (pinfunction "2_2") (pintype "passive"))
    )
    (net (code "164") (name "Net-(Q1-A1)") (class "Default")
      (node (ref "Q1") (pin "1") (pinfunction "A1_1") (pintype "input"))
      (node (ref "Q1") (pin "2") (pinfunction "B1_2") (pintype "input"))
      (node (ref "Q13") (pin "15") (pinfunction "TC_15") (pintype "input"))
    )
    (net (code "165") (name "Net-(Q1-A2)") (class "Default")
      (node (ref "Q1") (pin "3") (pinfunction "Y1_3") (pintype "input"))
      (node (ref "Q1") (pin "4") (pinfunction "A2_4") (pintype "input"))
    )
    (net (code "166") (name "Net-(Q1-A3)") (class "Default")
      (node (ref "Q1") (pin "6") (pinfunction "Y2_6") (pintype "input"))
      (node (ref "Q1") (pin "9") (pinfunction "A3_9") (pintype "input"))
    )
    (net (code "167") (name "Net-(Q1-B3)") (class "Default")
      (node (ref "Q1") (pin "10") (pinfunction "B3_10") (pintype "input"))
      (node (ref "Q1") (pin "11") (pinfunction "Y4_11") (pintype "input"))
    )
    (net (code "168") (name "Net-(Q1-Y3)") (class "Default")
      (node (ref "Q1") (pin "8") (pinfunction "Y3_8") (pintype "input"))
      (node (ref "Q12") (pin "2") (pinfunction "CP_2") (pintype "input"))
    )
    (net (code "169") (name "Net-(Q2-A2)") (class "Default")
      (node (ref "Q2") (pin "3") (pinfunction "Y1_3") (pintype "input"))
      (node (ref "Q2") (pin "4") (pinfunction "A2_4") (pintype "input"))
    )
    (net (code "170") (name "Net-(Q2-A3)") (class "Default")
      (node (ref "Q2") (pin "6") (pinfunction "Y2_6") (pintype "input"))
      (node (ref "Q2") (pin "9") (pinfunction "A3_9") (pintype "input"))
    )
    (net (code "171") (name "Net-(Q2-B3)") (class "Default")
      (node (ref "Q2") (pin "10") (pinfunction "B3_10") (pintype "input"))
      (node (ref "Q2") (pin "11") (pinfunction "Y4_11") (pintype "input"))
    )
    (net (code "172") (name "Net-(Q3-A2)") (class "Default")
      (node (ref "Q3") (pin "3") (pinfunction "Y1_3") (pintype "input"))
      (node (ref "Q3") (pin "4") (pinfunction "A2_4") (pintype "input"))
    )
    (net (code "173") (name "Net-(Q3-A3)") (class "Default")
      (node (ref "Q3") (pin "6") (pinfunction "Y2_6") (pintype "input"))
      (node (ref "Q3") (pin "9") (pinfunction "A3_9") (pintype "input"))
    )
    (net (code "174") (name "Net-(Q3-B3)") (class "Default")
      (node (ref "Q3") (pin "10") (pinfunction "B3_10") (pintype "input"))
      (node (ref "Q3") (pin "11") (pinfunction "Y4_11") (pintype "input"))
    )
    (net (code "175") (name "Net-(Q3-B4)") (class "Default")
      (node (ref "Q3") (pin "13") (pinfunction "B4_13") (pintype "input"))
      (node (ref "Q4") (pin "2") (pinfunction "Y1_2") (pintype "input"))
    )
    (net (code "176") (name "Net-(Q9-A2)") (class "Default")
      (node (ref "Q9") (pin "3") (pinfunction "Y1_3") (pintype "input"))
      (node (ref "Q9") (pin "4") (pinfunction "A2_4") (pintype "input"))
      (node (ref "Q9") (pin "5") (pinfunction "B2_5") (pintype "input"))
    )
    (net (code "177") (name "Net-(Q9-A4)") (class "Default")
      (node (ref "Q9") (pin "12") (pinfunction "A4_12") (pintype "input"))
      (node (ref "Q9") (pin "6") (pinfunction "Y2_6") (pintype "input"))
    )
    (net (code "178") (name "Net-(Q10-A2)") (class "Default")
      (node (ref "Q10") (pin "3") (pinfunction "Y1_3") (pintype "input"))
      (node (ref "Q10") (pin "4") (pinfunction "A2_4") (pintype "input"))
      (node (ref "Q10") (pin "5") (pinfunction "B2_5") (pintype "input"))
    )
    (net (code "179") (name "Net-(Q10-A4)") (class "Default")
      (node (ref "Q10") (pin "12") (pinfunction "A4_12") (pintype "input"))
      (node (ref "Q10") (pin "6") (pinfunction "Y2_6") (pintype "input"))
    )
    (net (code "180") (name "Net-(Q13-CP)") (class "Default")
      (node (ref "Q13") (pin "2") (pinfunction "CP_2") (pintype "input"))
      (node (ref "Q2") (pin "8") (pinfunction "Y3_8") (pintype "input"))
    )
    (net (code "181") (name "Net-(Q14-CP)") (class "Default")
      (node (ref "Q14") (pin "2") (pinfunction "CP_2") (pintype "input"))
      (node (ref "Q3") (pin "8") (pinfunction "Y3_8") (pintype "input"))
    )
    (net (code "182") (name "Net-(Q14-TC)") (class "Default")
      (node (ref "Q14") (pin "15") (pinfunction "TC_15") (pintype "input"))
      (node (ref "Q2") (pin "1") (pinfunction "A1_1") (pintype "input"))
      (node (ref "Q2") (pin "2") (pinfunction "B1_2") (pintype "input"))
    )
    (net (code "183") (name "Net-(Q15-TC)") (class "Default")
      (node (ref "Q15") (pin "15") (pinfunction "TC_15") (pintype "input"))
      (node (ref "Q3") (pin "1") (pinfunction "A1_1") (pintype "input"))
      (node (ref "Q3") (pin "2") (pinfunction "B1_2") (pintype "input"))
    )
    (net (code "184") (name "Net-(Q20-A2)") (class "Default")
      (node (ref "Q20") (pin "3") (pinfunction "Y1_3") (pintype "input"))
      (node (ref "Q20") (pin "4") (pinfunction "A2_4") (pintype "input"))
      (node (ref "Q20") (pin "5") (pinfunction "B2_5") (pintype "input"))
    )
    (net (code "185") (name "Net-(Q20-A4)") (class "Default")
      (node (ref "Q20") (pin "12") (pinfunction "A4_12") (pintype "input"))
      (node (ref "Q20") (pin "6") (pinfunction "Y2_6") (pintype "input"))
    )
    (net (code "186") (name "Net-(Q21-A2)") (class "Default")
      (node (ref "Q21") (pin "3") (pinfunction "Y1_3") (pintype "input"))
      (node (ref "Q21") (pin "4") (pinfunction "A2_4") (pintype "input"))
      (node (ref "Q21") (pin "5") (pinfunction "B2_5") (pintype "input"))
    )
    (net (code "187") (name "Net-(Q21-A4)") (class "Default")
      (node (ref "Q21") (pin "12") (pinfunction "A4_12") (pintype "input"))
      (node (ref "Q21") (pin "6") (pinfunction "Y2_6") (pintype "input"))
    )
    (net (code "188") (name "VCC") (class "Default")
      (node (ref "D1") (pin "1") (pinfunction "A_1") (pintype "passive"))
      (node (ref "D10") (pin "1") (pinfunction "A_1") (pintype "passive"))
      (node (ref "D11") (pin "1") (pinfunction "A_1") (pintype "passive"))
      (node (ref "D12") (pin "1") (pinfunction "A_1") (pintype "passive"))
      (node (ref "D13") (pin "1") (pinfunction "A_1") (pintype "passive"))
      (node (ref "D14") (pin "1") (pinfunction "A_1") (pintype "passive"))
      (node (ref "D15") (pin "1") (pinfunction "A_1") (pintype "passive"))
      (node (ref "D16") (pin "1") (pinfunction "A_1") (pintype "passive"))
      (node (ref "D2") (pin "1") (pinfunction "A_1") (pintype "passive"))
      (node (ref "D3") (pin "1") (pinfunction "A_1") (pintype "passive"))
      (node (ref "D4") (pin "1") (pinfunction "A_1") (pintype "passive"))
      (node (ref "D5") (pin "1") (pinfunction "A_1") (pintype "passive"))
      (node (ref "D6") (pin "1") (pinfunction "A_1") (pintype "passive"))
      (node (ref "D7") (pin "1") (pinfunction "A_1") (pintype "passive"))
      (node (ref "D8") (pin "1") (pinfunction "A_1") (pintype "passive"))
      (node (ref "D9") (pin "1") (pinfunction "A_1") (pintype "passive"))
      (node (ref "Q1") (pin "14") (pinfunction "Vcc_14") (pintype "input"))
      (node (ref "Q10") (pin "14") (pinfunction "Vcc_14") (pintype "input"))
      (node (ref "Q11") (pin "14") (pinfunction "Vcc_14") (pintype "input"))
      (node (ref "Q12") (pin "16") (pinfunction "Vcc_16") (pintype "input"))
      (node (ref "Q12") (pin "7") (pinfunction "CEP_7") (pintype "input"))
      (node (ref "Q13") (pin "16") (pinfunction "Vcc_16") (pintype "input"))
      (node (ref "Q13") (pin "7") (pinfunction "CEP_7") (pintype "input"))
      (node (ref "Q14") (pin "16") (pinfunction "Vcc_16") (pintype "input"))
      (node (ref "Q14") (pin "7") (pinfunction "CEP_7") (pintype "input"))
      (node (ref "Q15") (pin "16") (pinfunction "Vcc_16") (pintype "input"))
      (node (ref "Q15") (pin "7") (pinfunction "CEP_7") (pintype "input"))
      (node (ref "Q16") (pin "16") (pinfunction "VCC_16") (pintype "input"))
      (node (ref "Q17") (pin "16") (pinfunction "VCC_16") (pintype "input"))
      (node (ref "Q18") (pin "16") (pinfunction "VCC_16") (pintype "input"))
      (node (ref "Q19") (pin "16") (pinfunction "VCC_16") (pintype "input"))
      (node (ref "Q2") (pin "14") (pinfunction "Vcc_14") (pintype "input"))
      (node (ref "Q20") (pin "14") (pinfunction "Vcc_14") (pintype "input"))
      (node (ref "Q21") (pin "14") (pinfunction "Vcc_14") (pintype "input"))
      (node (ref "Q22") (pin "20") (pinfunction "Vcc_20") (pintype "input"))
      (node (ref "Q23") (pin "20") (pinfunction "Vcc_20") (pintype "input"))
      (node (ref "Q24") (pin "20") (pinfunction "Vcc_20") (pintype "input"))
      (node (ref "Q25") (pin "20") (pinfunction "Vcc_20") (pintype "input"))
      (node (ref "Q26") (pin "16") (pinfunction "Vcc_16") (pintype "input"))
      (node (ref "Q27") (pin "16") (pinfunction "Vcc_16") (pintype "input"))
      (node (ref "Q28") (pin "16") (pinfunction "Vcc_16") (pintype "input"))
      (node (ref "Q29") (pin "16") (pinfunction "Vcc_16") (pintype "input"))
      (node (ref "Q3") (pin "14") (pinfunction "Vcc_14") (pintype "input"))
      (node (ref "Q30") (pin "24") (pinfunction "VCC_24") (pintype "input"))
      (node (ref "Q31") (pin "24") (pinfunction "VCC_24") (pintype "input"))
      (node (ref "Q32") (pin "24") (pinfunction "VCC_24") (pintype "input"))
      (node (ref "Q33") (pin "24") (pinfunction "VCC_24") (pintype "input"))
      (node (ref "Q34") (pin "30") (pinfunction "CE2_30") (pintype "input"))
      (node (ref "Q34") (pin "32") (pinfunction "VCC_32") (pintype "input"))
      (node (ref "Q35") (pin "20") (pinfunction "Vcc_20") (pintype "input"))
      (node (ref "Q36") (pin "20") (pinfunction "Vcc_20") (pintype "input"))
      (node (ref "Q37") (pin "20") (pinfunction "Vcc_20") (pintype "input"))
      (node (ref "Q38") (pin "20") (pinfunction "Vcc_20") (pintype "input"))
      (node (ref "Q39") (pin "20") (pinfunction "Vcc_20") (pintype "input"))
      (node (ref "Q4") (pin "14") (pinfunction "Vcc_14") (pintype "input"))
      (node (ref "Q40") (pin "20") (pinfunction "Vcc_20") (pintype "input"))
      (node (ref "Q41") (pin "20") (pinfunction "Vcc_20") (pintype "input"))
      (node (ref "Q42") (pin "20") (pinfunction "Vcc_20") (pintype "input"))
      (node (ref "Q43") (pin "20") (pinfunction "Vcc_20") (pintype "input"))
      (node (ref "Q5") (pin "16") (pinfunction "VCC_16") (pintype "input"))
      (node (ref "Q6") (pin "16") (pinfunction "VCC_16") (pintype "input"))
      (node (ref "Q7") (pin "16") (pinfunction "VCC_16") (pintype "input"))
      (node (ref "Q8") (pin "16") (pinfunction "VCC_16") (pintype "input"))
      (node (ref "Q9") (pin "14") (pinfunction "Vcc_14") (pintype "input"))
    )
    (net (code "189") (name "unconnected-(Q4-A2-Pad3)") (class "Default")
      (node (ref "Q4") (pin "3") (pinfunction "A2_3") (pintype "input"))
    )
    (net (code "190") (name "unconnected-(Q4-A3-Pad5)") (class "Default")
      (node (ref "Q4") (pin "5") (pinfunction "A3_5") (pintype "input"))
    )
    (net (code "191") (name "unconnected-(Q4-A5-Pad11)") (class "Default")
      (node (ref "Q4") (pin "11") (pinfunction "A5_11") (pintype "input"))
    )
    (net (code "192") (name "unconnected-(Q4-A7-Pad9)") (class "Default")
      (node (ref "Q4") (pin "9") (pinfunction "A7_9") (pintype "input"))
    )
    (net (code "193") (name "unconnected-(Q4-Y2-Pad4)") (class "Default")
      (node (ref "Q4") (pin "4") (pinfunction "Y2_4") (pintype "input"))
    )
    (net (code "194") (name "unconnected-(Q4-Y3-Pad6)") (class "Default")
      (node (ref "Q4") (pin "6") (pinfunction "Y3_6") (pintype "input"))
    )
    (net (code "195") (name "unconnected-(Q4-Y5-Pad10)") (class "Default")
      (node (ref "Q4") (pin "10") (pinfunction "Y5_10") (pintype "input"))
    )
    (net (code "196") (name "unconnected-(Q4-Y7-Pad8)") (class "Default")
      (node (ref "Q4") (pin "8") (pinfunction "Y7_8") (pintype "input"))
    )
    (net (code "197") (name "unconnected-(Q9-A3-Pad9)") (class "Default")
      (node (ref "Q9") (pin "9") (pinfunction "A3_9") (pintype "input"))
    )
    (net (code "198") (name "unconnected-(Q9-B3-Pad10)") (class "Default")
      (node (ref "Q9") (pin "10") (pinfunction "B3_10") (pintype "input"))
    )
    (net (code "199") (name "unconnected-(Q9-Y3-Pad8)") (class "Default")
      (node (ref "Q9") (pin "8") (pinfunction "Y3_8") (pintype "input"))
    )
    (net (code "200") (name "unconnected-(Q10-A3-Pad9)") (class "Default")
      (node (ref "Q10") (pin "9") (pinfunction "A3_9") (pintype "input"))
    )
    (net (code "201") (name "unconnected-(Q10-B3-Pad10)") (class "Default")
      (node (ref "Q10") (pin "10") (pinfunction "B3_10") (pintype "input"))
    )
    (net (code "202") (name "unconnected-(Q10-Y3-Pad8)") (class "Default")
      (node (ref "Q10") (pin "8") (pinfunction "Y3_8") (pintype "input"))
    )
    (net (code "203") (name "unconnected-(Q11-A5-Pad11)") (class "Default")
      (node (ref "Q11") (pin "11") (pinfunction "A5_11") (pintype "input"))
    )
    (net (code "204") (name "unconnected-(Q11-A6-Pad13)") (class "Default")
      (node (ref "Q11") (pin "13") (pinfunction "A6_13") (pintype "input"))
    )
    (net (code "205") (name "unconnected-(Q11-A7-Pad9)") (class "Default")
      (node (ref "Q11") (pin "9") (pinfunction "A7_9") (pintype "input"))
    )
    (net (code "206") (name "unconnected-(Q11-Y5-Pad10)") (class "Default")
      (node (ref "Q11") (pin "10") (pinfunction "Y5_10") (pintype "input"))
    )
    (net (code "207") (name "unconnected-(Q11-Y6-Pad12)") (class "Default")
      (node (ref "Q11") (pin "12") (pinfunction "Y6_12") (pintype "input"))
    )
    (net (code "208") (name "unconnected-(Q11-Y7-Pad8)") (class "Default")
      (node (ref "Q11") (pin "8") (pinfunction "Y7_8") (pintype "input"))
    )
    (net (code "209") (name "unconnected-(Q12-TC-Pad15)") (class "Default")
      (node (ref "Q12") (pin "15") (pinfunction "TC_15") (pintype "input"))
    )
    (net (code "210") (name "unconnected-(Q20-A3-Pad9)") (class "Default")
      (node (ref "Q20") (pin "9") (pinfunction "A3_9") (pintype "input"))
    )
    (net (code "211") (name "unconnected-(Q20-B3-Pad10)") (class "Default")
      (node (ref "Q20") (pin "10") (pinfunction "B3_10") (pintype "input"))
    )
    (net (code "212") (name "unconnected-(Q20-Y3-Pad8)") (class "Default")
      (node (ref "Q20") (pin "8") (pinfunction "Y3_8") (pintype "input"))
    )
    (net (code "213") (name "unconnected-(Q21-A3-Pad9)") (class "Default")
      (node (ref "Q21") (pin "9") (pinfunction "A3_9") (pintype "input"))
    )
    (net (code "214") (name "unconnected-(Q21-B3-Pad10)") (class "Default")
      (node (ref "Q21") (pin "10") (pinfunction "B3_10") (pintype "input"))
    )
    (net (code "215") (name "unconnected-(Q21-Y3-Pad8)") (class "Default")
      (node (ref "Q21") (pin "8") (pinfunction "Y3_8") (pintype "input"))
    )
    (net (code "216") (name "unconnected-(Q26-(G1)-Pad9)") (class "Default")
      (node (ref "Q26") (pin "9") (pinfunction "(G1)_9") (pintype "input"))
    )
    (net (code "217") (name "unconnected-(Q26-(G2)-Pad10)") (class "Default")
      (node (ref "Q26") (pin "10") (pinfunction "(G2)_10") (pintype "input"))
    )
    (net (code "218") (name "unconnected-(Q26-CLK-Pad7)") (class "Default")
      (node (ref "Q26") (pin "7") (pinfunction "CLK_7") (pintype "input"))
    )
    (net (code "219") (name "unconnected-(Q27-(G1)-Pad9)") (class "Default")
      (node (ref "Q27") (pin "9") (pinfunction "(G1)_9") (pintype "input"))
    )
    (net (code "220") (name "unconnected-(Q27-(G2)-Pad10)") (class "Default")
      (node (ref "Q27") (pin "10") (pinfunction "(G2)_10") (pintype "input"))
    )
    (net (code "221") (name "unconnected-(Q27-CLK-Pad7)") (class "Default")
      (node (ref "Q27") (pin "7") (pinfunction "CLK_7") (pintype "input"))
    )
    (net (code "222") (name "unconnected-(Q28-(G1)-Pad9)") (class "Default")
      (node (ref "Q28") (pin "9") (pinfunction "(G1)_9") (pintype "input"))
    )
    (net (code "223") (name "unconnected-(Q28-(G2)-Pad10)") (class "Default")
      (node (ref "Q28") (pin "10") (pinfunction "(G2)_10") (pintype "input"))
    )
    (net (code "224") (name "unconnected-(Q28-CLK-Pad7)") (class "Default")
      (node (ref "Q28") (pin "7") (pinfunction "CLK_7") (pintype "input"))
    )
    (net (code "225") (name "unconnected-(Q29-(G1)-Pad9)") (class "Default")
      (node (ref "Q29") (pin "9") (pinfunction "(G1)_9") (pintype "input"))
    )
    (net (code "226") (name "unconnected-(Q29-(G2)-Pad10)") (class "Default")
      (node (ref "Q29") (pin "10") (pinfunction "(G2)_10") (pintype "input"))
    )
    (net (code "227") (name "unconnected-(Q29-CLK-Pad7)") (class "Default")
      (node (ref "Q29") (pin "7") (pinfunction "CLK_7") (pintype "input"))
    )
    (net (code "228") (name "unconnected-(Q30-A=B-Pad14)") (class "Default")
      (node (ref "Q30") (pin "14") (pinfunction "A=B_14") (pintype "input"))
    )
    (net (code "229") (name "unconnected-(Q30-CN+4-Pad16)") (class "Default")
      (node (ref "Q30") (pin "16") (pinfunction "CN+4_16") (pintype "input"))
    )
    (net (code "230") (name "unconnected-(Q30-GP-Pad17)") (class "Default")
      (node (ref "Q30") (pin "17") (pinfunction "GP_17") (pintype "input"))
    )
    (net (code "231") (name "unconnected-(Q30-PP-Pad15)") (class "Default")
      (node (ref "Q30") (pin "15") (pinfunction "PP_15") (pintype "input"))
    )
    (net (code "232") (name "unconnected-(Q31-A=B-Pad14)") (class "Default")
      (node (ref "Q31") (pin "14") (pinfunction "A=B_14") (pintype "input"))
    )
    (net (code "233") (name "unconnected-(Q31-GP-Pad17)") (class "Default")
      (node (ref "Q31") (pin "17") (pinfunction "GP_17") (pintype "input"))
    )
    (net (code "234") (name "unconnected-(Q31-PP-Pad15)") (class "Default")
      (node (ref "Q31") (pin "15") (pinfunction "PP_15") (pintype "input"))
    )
    (net (code "235") (name "unconnected-(Q32-A=B-Pad14)") (class "Default")
      (node (ref "Q32") (pin "14") (pinfunction "A=B_14") (pintype "input"))
    )
    (net (code "236") (name "unconnected-(Q32-GP-Pad17)") (class "Default")
      (node (ref "Q32") (pin "17") (pinfunction "GP_17") (pintype "input"))
    )
    (net (code "237") (name "unconnected-(Q32-PP-Pad15)") (class "Default")
      (node (ref "Q32") (pin "15") (pinfunction "PP_15") (pintype "input"))
    )
    (net (code "238") (name "unconnected-(Q33-A=B-Pad14)") (class "Default")
      (node (ref "Q33") (pin "14") (pinfunction "A=B_14") (pintype "input"))
    )
    (net (code "239") (name "unconnected-(Q33-CN-Pad7)") (class "Default")
      (node (ref "Q33") (pin "7") (pinfunction "CN_7") (pintype "input"))
    )
    (net (code "240") (name "unconnected-(Q33-GP-Pad17)") (class "Default")
      (node (ref "Q33") (pin "17") (pinfunction "GP_17") (pintype "input"))
    )
    (net (code "241") (name "unconnected-(Q33-PP-Pad15)") (class "Default")
      (node (ref "Q33") (pin "15") (pinfunction "PP_15") (pintype "input"))
    )
    (net (code "242") (name "unconnected-(Q35-(E)-Pad19)") (class "Default")
      (node (ref "Q35") (pin "19") (pinfunction "(E)_19") (pintype "input"))
    )
    (net (code "243") (name "unconnected-(Q35-DIR-Pad1)") (class "Default")
      (node (ref "Q35") (pin "1") (pinfunction "DIR_1") (pintype "input"))
    )
  )
)
